# Stepoko.net
KiCad netlist of a schematic drawn in EAGLE
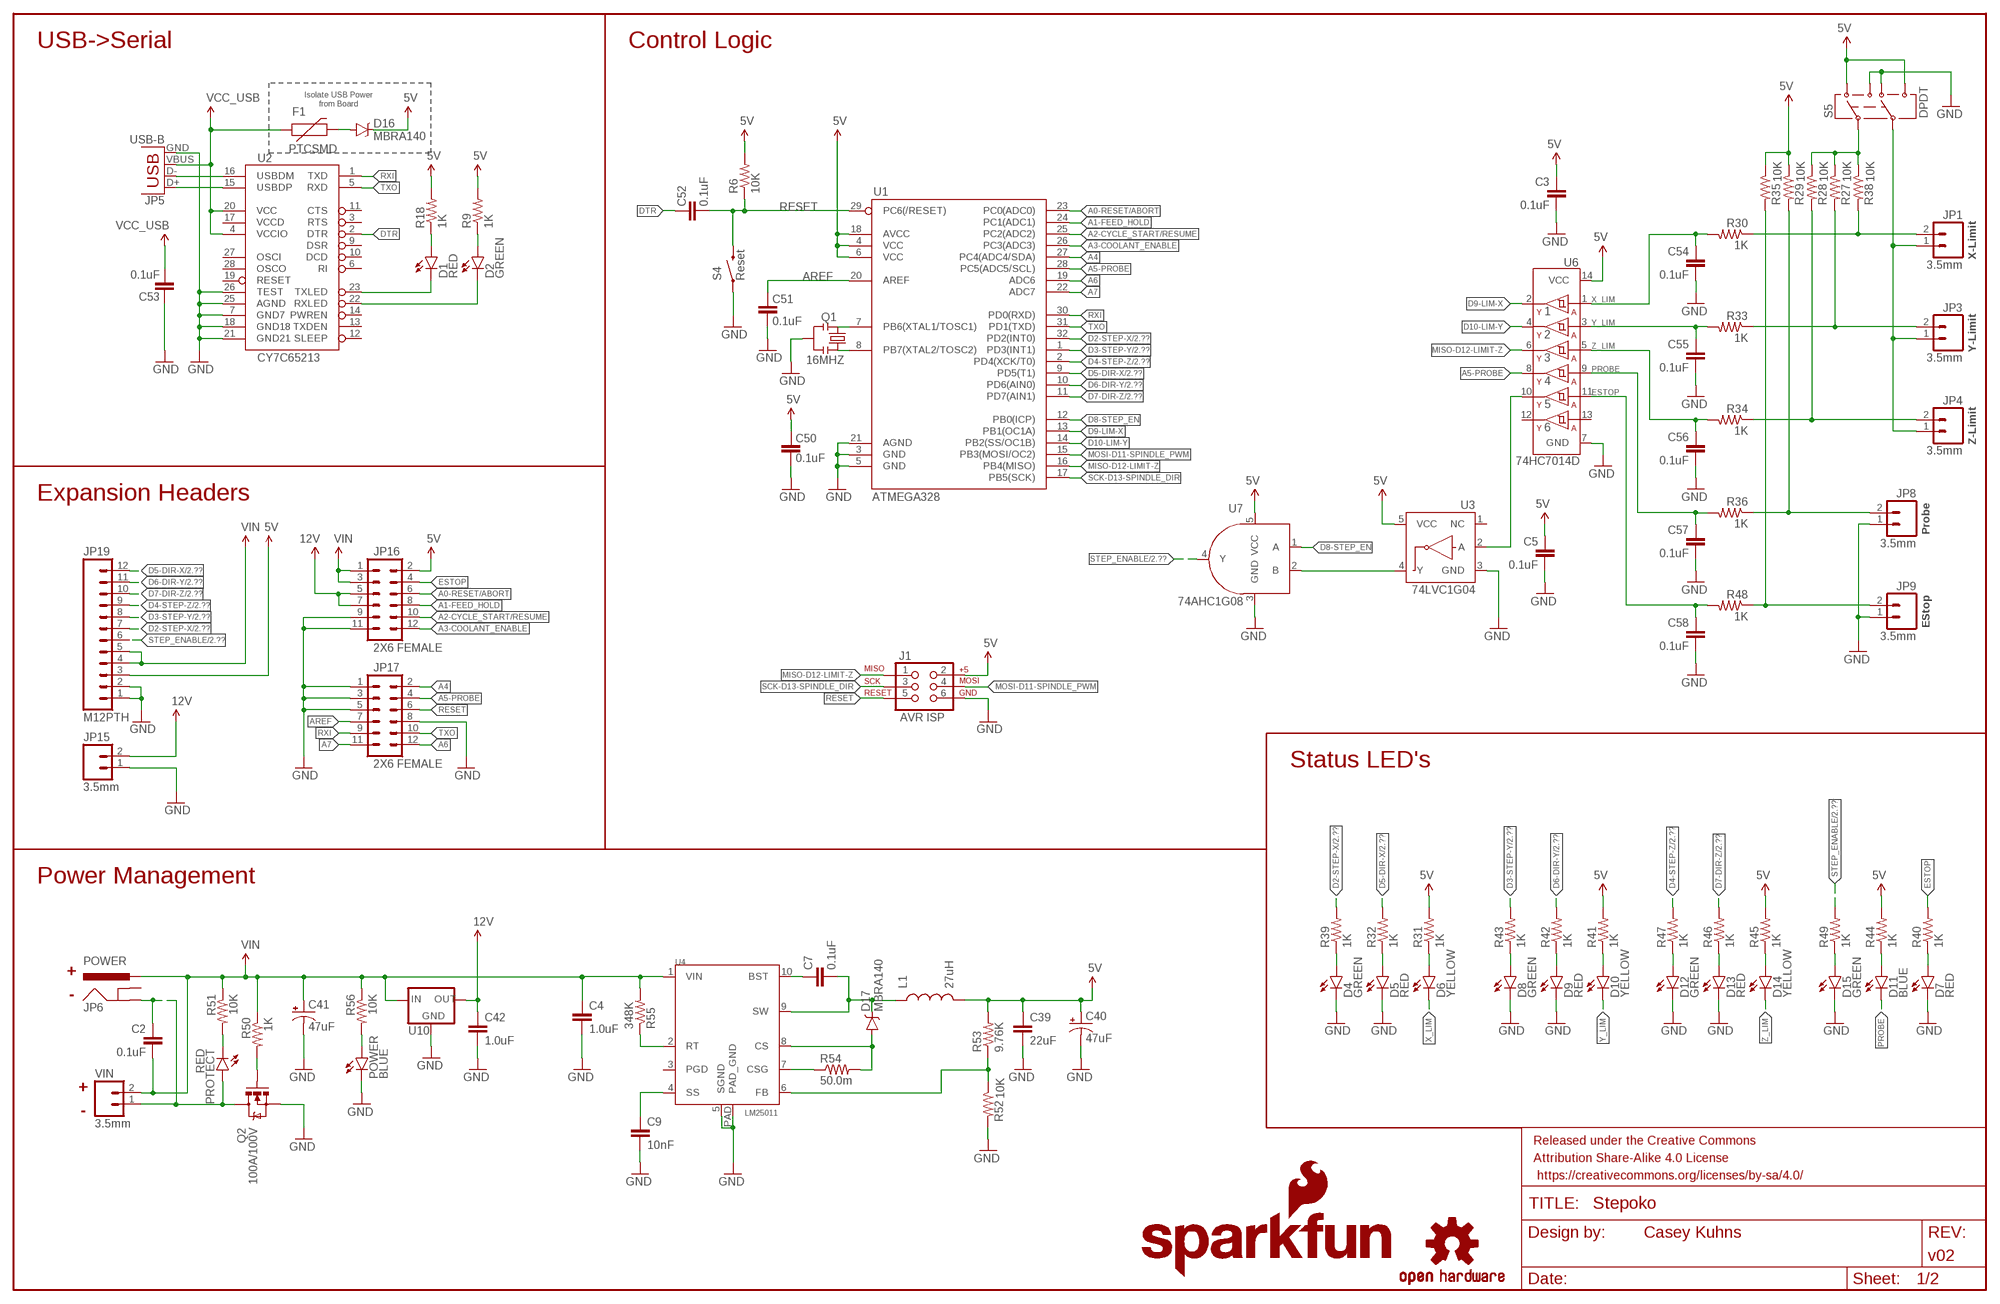
[diagram p0: schematic, sheet 1]
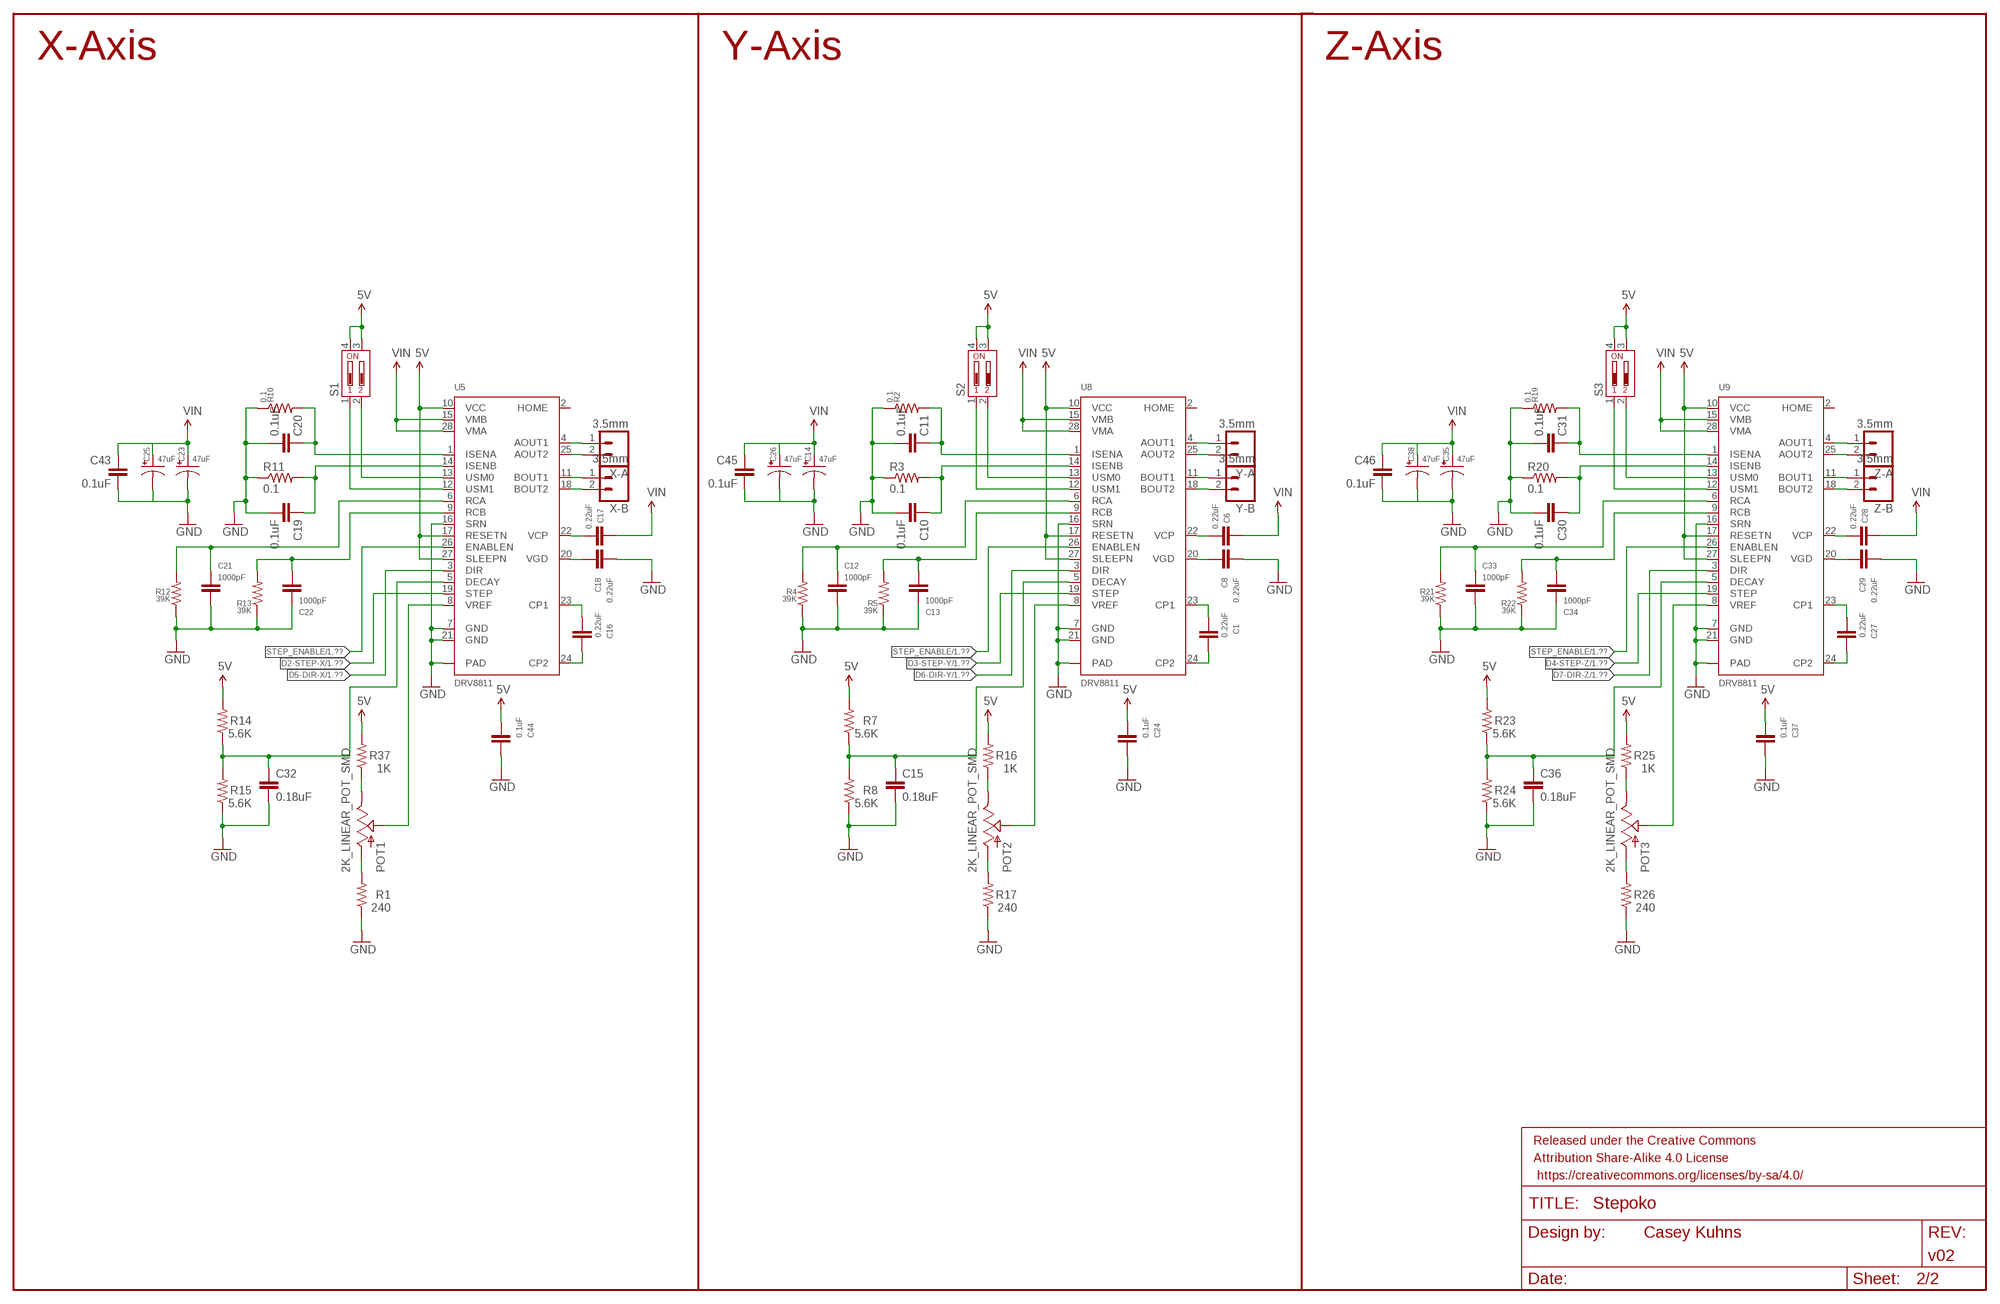
[diagram p1: schematic, sheet 2]

(export (version "E")
  (design (tool "Eeschema 10.0.6"))
  (components
    (comp (ref "C1")
      (value "0.22uF")
      (footprint "eagle-import:0603-CAP")
      (libsource (lib "eagle-import") (part "0.22UF50V-20%,+80%(0603)"))
    )
    (comp (ref "C6")
      (value "0.22uF")
      (footprint "eagle-import:0603-CAP")
      (libsource (lib "eagle-import") (part "0.22UF50V-20%,+80%(0603)"))
    )
    (comp (ref "C8")
      (value "0.22uF")
      (footprint "eagle-import:0603-CAP")
      (libsource (lib "eagle-import") (part "0.22UF50V-20%,+80%(0603)"))
    )
    (comp (ref "C10")
      (value "0.1uF")
      (footprint "eagle-import:0603-CAP")
      (libsource (lib "eagle-import") (part "0.1UF-25V(+80/-20%)(0603)"))
    )
    (comp (ref "C11")
      (value "0.1uF")
      (footprint "eagle-import:0603-CAP")
      (libsource (lib "eagle-import") (part "0.1UF-25V(+80/-20%)(0603)"))
    )
    (comp (ref "C12")
      (value "1000pF")
      (footprint "eagle-import:0603-CAP")
      (libsource (lib "eagle-import") (part "1NF/1000PF-50V-10%(0603)"))
    )
    (comp (ref "C13")
      (value "1000pF")
      (footprint "eagle-import:0603-CAP")
      (libsource (lib "eagle-import") (part "1NF/1000PF-50V-10%(0603)"))
    )
    (comp (ref "C14")
      (value "47uF")
      (footprint "eagle-import:PANASONIC_D")
      (libsource (lib "eagle-import") (part "47UF-50V-20%(ELECT)"))
    )
    (comp (ref "C15")
      (value "0.18uF")
      (footprint "eagle-import:0603")
      (libsource (lib "eagle-import") (part "0.18UF-10V(+-10%)(0603)"))
    )
    (comp (ref "C16")
      (value "0.22uF")
      (footprint "eagle-import:0603-CAP")
      (libsource (lib "eagle-import") (part "0.22UF50V-20%,+80%(0603)"))
    )
    (comp (ref "C17")
      (value "0.22uF")
      (footprint "eagle-import:0603-CAP")
      (libsource (lib "eagle-import") (part "0.22UF50V-20%,+80%(0603)"))
    )
    (comp (ref "C18")
      (value "0.22uF")
      (footprint "eagle-import:0603-CAP")
      (libsource (lib "eagle-import") (part "0.22UF50V-20%,+80%(0603)"))
    )
    (comp (ref "C19")
      (value "0.1uF")
      (footprint "eagle-import:0603-CAP")
      (libsource (lib "eagle-import") (part "0.1UF-25V(+80/-20%)(0603)"))
    )
    (comp (ref "C20")
      (value "0.1uF")
      (footprint "eagle-import:0603-CAP")
      (libsource (lib "eagle-import") (part "0.1UF-25V(+80/-20%)(0603)"))
    )
    (comp (ref "C21")
      (value "1000pF")
      (footprint "eagle-import:0603-CAP")
      (libsource (lib "eagle-import") (part "1NF/1000PF-50V-10%(0603)"))
    )
    (comp (ref "C22")
      (value "1000pF")
      (footprint "eagle-import:0603-CAP")
      (libsource (lib "eagle-import") (part "1NF/1000PF-50V-10%(0603)"))
    )
    (comp (ref "C23")
      (value "47uF")
      (footprint "eagle-import:PANASONIC_D")
      (libsource (lib "eagle-import") (part "47UF-50V-20%(ELECT)"))
    )
    (comp (ref "C24")
      (value "0.1uF")
      (footprint "eagle-import:0603-CAP")
      (libsource (lib "eagle-import") (part "0.1UF-25V(+80/-20%)(0603)"))
    )
    (comp (ref "C25")
      (value "47uF")
      (footprint "eagle-import:PANASONIC_D")
      (libsource (lib "eagle-import") (part "47UF-50V-20%(ELECT)"))
    )
    (comp (ref "C26")
      (value "47uF")
      (footprint "eagle-import:PANASONIC_D")
      (libsource (lib "eagle-import") (part "47UF-50V-20%(ELECT)"))
    )
    (comp (ref "C27")
      (value "0.22uF")
      (footprint "eagle-import:0603-CAP")
      (libsource (lib "eagle-import") (part "0.22UF50V-20%,+80%(0603)"))
    )
    (comp (ref "C28")
      (value "0.22uF")
      (footprint "eagle-import:0603-CAP")
      (libsource (lib "eagle-import") (part "0.22UF50V-20%,+80%(0603)"))
    )
    (comp (ref "C29")
      (value "0.22uF")
      (footprint "eagle-import:0603-CAP")
      (libsource (lib "eagle-import") (part "0.22UF50V-20%,+80%(0603)"))
    )
    (comp (ref "C30")
      (value "0.1uF")
      (footprint "eagle-import:0603-CAP")
      (libsource (lib "eagle-import") (part "0.1UF-25V(+80/-20%)(0603)"))
    )
    (comp (ref "C31")
      (value "0.1uF")
      (footprint "eagle-import:0603-CAP")
      (libsource (lib "eagle-import") (part "0.1UF-25V(+80/-20%)(0603)"))
    )
    (comp (ref "C32")
      (value "0.18uF")
      (footprint "eagle-import:0603")
      (libsource (lib "eagle-import") (part "0.18UF-10V(+-10%)(0603)"))
    )
    (comp (ref "C33")
      (value "1000pF")
      (footprint "eagle-import:0603-CAP")
      (libsource (lib "eagle-import") (part "1NF/1000PF-50V-10%(0603)"))
    )
    (comp (ref "C34")
      (value "1000pF")
      (footprint "eagle-import:0603-CAP")
      (libsource (lib "eagle-import") (part "1NF/1000PF-50V-10%(0603)"))
    )
    (comp (ref "C35")
      (value "47uF")
      (footprint "eagle-import:PANASONIC_D")
      (libsource (lib "eagle-import") (part "47UF-50V-20%(ELECT)"))
    )
    (comp (ref "C36")
      (value "0.18uF")
      (footprint "eagle-import:0603")
      (libsource (lib "eagle-import") (part "0.18UF-10V(+-10%)(0603)"))
    )
    (comp (ref "C37")
      (value "0.1uF")
      (footprint "eagle-import:0603-CAP")
      (libsource (lib "eagle-import") (part "0.1UF-25V(+80/-20%)(0603)"))
    )
    (comp (ref "C38")
      (value "47uF")
      (footprint "eagle-import:PANASONIC_D")
      (libsource (lib "eagle-import") (part "47UF-50V-20%(ELECT)"))
    )
    (comp (ref "C43")
      (value "0.1uF")
      (footprint "eagle-import:0603-CAP")
      (libsource (lib "eagle-import") (part "0.1UF-25V(+80/-20%)(0603)"))
    )
    (comp (ref "C44")
      (value "0.1uF")
      (footprint "eagle-import:0603-CAP")
      (libsource (lib "eagle-import") (part "0.1UF-25V(+80/-20%)(0603)"))
    )
    (comp (ref "C45")
      (value "0.1uF")
      (footprint "eagle-import:0603-CAP")
      (libsource (lib "eagle-import") (part "0.1UF-25V(+80/-20%)(0603)"))
    )
    (comp (ref "C46")
      (value "0.1uF")
      (footprint "eagle-import:0603-CAP")
      (libsource (lib "eagle-import") (part "0.1UF-25V(+80/-20%)(0603)"))
    )
    (comp (ref "FRAME2")
      (value "FRAME-LEDGER")
      (footprint "eagle-import:CREATIVE_COMMONS")
      (fields (field (name "DESIGNER") "Casey Kuhns") (field (name "VERSION") "v02"))
      (libsource (lib "eagle-import") (part "FRAME-LEDGER"))
    )
    (comp (ref "POT1")
      (value "2K_LINEAR_POT_SMD")
      (footprint "eagle-import:TC33X")
      (libsource (lib "eagle-import") (part "2K_LINEAR_POT_SMD"))
    )
    (comp (ref "POT2")
      (value "2K_LINEAR_POT_SMD")
      (footprint "eagle-import:TC33X")
      (libsource (lib "eagle-import") (part "2K_LINEAR_POT_SMD"))
    )
    (comp (ref "POT3")
      (value "2K_LINEAR_POT_SMD")
      (footprint "eagle-import:TC33X")
      (libsource (lib "eagle-import") (part "2K_LINEAR_POT_SMD"))
    )
    (comp (ref "R1")
      (value "240")
      (footprint "eagle-import:0603-RES")
      (libsource (lib "eagle-import") (part "240OHM1/10W1%(0603)"))
    )
    (comp (ref "R2")
      (value "0.1")
      (footprint "eagle-import:1210")
      (libsource (lib "eagle-import") (part "0.1OHM-1/2W-1%(1210)"))
    )
    (comp (ref "R3")
      (value "0.1")
      (footprint "eagle-import:1210")
      (libsource (lib "eagle-import") (part "0.1OHM-1/2W-1%(1210)"))
    )
    (comp (ref "R4")
      (value "39K")
      (footprint "eagle-import:0603")
      (libsource (lib "eagle-import") (part "39KOHM-1/10W-1%(0603)"))
    )
    (comp (ref "R5")
      (value "39K")
      (footprint "eagle-import:0603")
      (libsource (lib "eagle-import") (part "39KOHM-1/10W-1%(0603)"))
    )
    (comp (ref "R7")
      (value "5.6K")
      (footprint "eagle-import:0603")
      (libsource (lib "eagle-import") (part "5.6KOHM-1/10W-1%(0603)"))
    )
    (comp (ref "R8")
      (value "5.6K")
      (footprint "eagle-import:0603")
      (libsource (lib "eagle-import") (part "5.6KOHM-1/10W-1%(0603)"))
    )
    (comp (ref "R10")
      (value "0.1")
      (footprint "eagle-import:1210")
      (libsource (lib "eagle-import") (part "0.1OHM-1/2W-1%(1210)"))
    )
    (comp (ref "R11")
      (value "0.1")
      (footprint "eagle-import:1210")
      (libsource (lib "eagle-import") (part "0.1OHM-1/2W-1%(1210)"))
    )
    (comp (ref "R12")
      (value "39K")
      (footprint "eagle-import:0603")
      (libsource (lib "eagle-import") (part "39KOHM-1/10W-1%(0603)"))
    )
    (comp (ref "R13")
      (value "39K")
      (footprint "eagle-import:0603")
      (libsource (lib "eagle-import") (part "39KOHM-1/10W-1%(0603)"))
    )
    (comp (ref "R14")
      (value "5.6K")
      (footprint "eagle-import:0603")
      (libsource (lib "eagle-import") (part "5.6KOHM-1/10W-1%(0603)"))
    )
    (comp (ref "R15")
      (value "5.6K")
      (footprint "eagle-import:0603")
      (libsource (lib "eagle-import") (part "5.6KOHM-1/10W-1%(0603)"))
    )
    (comp (ref "R16")
      (value "1K")
      (footprint "eagle-import:0603-RES")
      (libsource (lib "eagle-import") (part "1KOHM-1/10W-1%(0603)"))
    )
    (comp (ref "R17")
      (value "240")
      (footprint "eagle-import:0603-RES")
      (libsource (lib "eagle-import") (part "240OHM1/10W1%(0603)"))
    )
    (comp (ref "R19")
      (value "0.1")
      (footprint "eagle-import:1210")
      (libsource (lib "eagle-import") (part "0.1OHM-1/2W-1%(1210)"))
    )
    (comp (ref "R20")
      (value "0.1")
      (footprint "eagle-import:1210")
      (libsource (lib "eagle-import") (part "0.1OHM-1/2W-1%(1210)"))
    )
    (comp (ref "R21")
      (value "39K")
      (footprint "eagle-import:0603")
      (libsource (lib "eagle-import") (part "39KOHM-1/10W-1%(0603)"))
    )
    (comp (ref "R22")
      (value "39K")
      (footprint "eagle-import:0603")
      (libsource (lib "eagle-import") (part "39KOHM-1/10W-1%(0603)"))
    )
    (comp (ref "R23")
      (value "5.6K")
      (footprint "eagle-import:0603")
      (libsource (lib "eagle-import") (part "5.6KOHM-1/10W-1%(0603)"))
    )
    (comp (ref "R24")
      (value "5.6K")
      (footprint "eagle-import:0603")
      (libsource (lib "eagle-import") (part "5.6KOHM-1/10W-1%(0603)"))
    )
    (comp (ref "R25")
      (value "1K")
      (footprint "eagle-import:0603-RES")
      (libsource (lib "eagle-import") (part "1KOHM-1/10W-1%(0603)"))
    )
    (comp (ref "R26")
      (value "240")
      (footprint "eagle-import:0603-RES")
      (libsource (lib "eagle-import") (part "240OHM1/10W1%(0603)"))
    )
    (comp (ref "R37")
      (value "1K")
      (footprint "eagle-import:0603-RES")
      (libsource (lib "eagle-import") (part "1KOHM-1/10W-1%(0603)"))
    )
    (comp (ref "S1")
      (value "2-POS-DIPCTS-THRU-HOLE")
      (footprint "eagle-import:209-2LPST")
      (libsource (lib "eagle-import") (part "2-POS-DIPCTS-THRU-HOLE"))
    )
    (comp (ref "S2")
      (value "2-POS-DIPCTS-THRU-HOLE")
      (footprint "eagle-import:209-2LPST")
      (libsource (lib "eagle-import") (part "2-POS-DIPCTS-THRU-HOLE"))
    )
    (comp (ref "S3")
      (value "2-POS-DIPCTS-THRU-HOLE")
      (footprint "eagle-import:209-2LPST")
      (libsource (lib "eagle-import") (part "2-POS-DIPCTS-THRU-HOLE"))
    )
    (comp (ref "U5")
      (value "DRV8811")
      (footprint "eagle-import:HTSSOP28")
      (libsource (lib "eagle-import") (part "DRV8811"))
    )
    (comp (ref "U8")
      (value "DRV8811")
      (footprint "eagle-import:HTSSOP28")
      (libsource (lib "eagle-import") (part "DRV8811"))
    )
    (comp (ref "U9")
      (value "DRV8811")
      (footprint "eagle-import:HTSSOP28")
      (libsource (lib "eagle-import") (part "DRV8811"))
    )
    (comp (ref "X-A")
      (value "3.5mm")
      (footprint "eagle-import:SCREWTERMINAL-3.5MM-2_LOCK")
      (libsource (lib "eagle-import") (part "M023.5MM_LOCK"))
    )
    (comp (ref "X-B")
      (value "3.5mm")
      (footprint "eagle-import:SCREWTERMINAL-3.5MM-2_LOCK")
      (libsource (lib "eagle-import") (part "M023.5MM_LOCK"))
    )
    (comp (ref "Y-A")
      (value "3.5mm")
      (footprint "eagle-import:SCREWTERMINAL-3.5MM-2_LOCK")
      (libsource (lib "eagle-import") (part "M023.5MM_LOCK"))
    )
    (comp (ref "Y-B")
      (value "3.5mm")
      (footprint "eagle-import:SCREWTERMINAL-3.5MM-2_LOCK")
      (libsource (lib "eagle-import") (part "M023.5MM_LOCK"))
    )
    (comp (ref "Z-A")
      (value "3.5mm")
      (footprint "eagle-import:SCREWTERMINAL-3.5MM-2_LOCK")
      (libsource (lib "eagle-import") (part "M023.5MM_LOCK"))
    )
    (comp (ref "Z-B")
      (value "3.5mm")
      (footprint "eagle-import:SCREWTERMINAL-3.5MM-2_LOCK")
      (libsource (lib "eagle-import") (part "M023.5MM_LOCK"))
    )
    (comp (ref "C2")
      (value "0.1uF")
      (footprint "eagle-import:0603-CAP")
      (libsource (lib "eagle-import") (part "0.1UF-100V-10%(0603)"))
    )
    (comp (ref "C3")
      (value "0.1uF")
      (footprint "eagle-import:0603-CAP")
      (libsource (lib "eagle-import") (part "0.1UF-25V(+80/-20%)(0603)"))
    )
    (comp (ref "C4")
      (value "1.0uF")
      (footprint "eagle-import:1206")
      (libsource (lib "eagle-import") (part "1.0UF50V10%(1206)"))
    )
    (comp (ref "C5")
      (value "0.1uF")
      (footprint "eagle-import:0603-CAP")
      (libsource (lib "eagle-import") (part "0.1UF-25V(+80/-20%)(0603)"))
    )
    (comp (ref "C7")
      (value "0.1uF")
      (footprint "eagle-import:0603-CAP")
      (libsource (lib "eagle-import") (part "0.1UF-25V(+80/-20%)(0603)"))
    )
    (comp (ref "C9")
      (value "10nF")
      (footprint "eagle-import:0603-CAP")
      (libsource (lib "eagle-import") (part "10NF/10000PF-50V-10%(0603)"))
    )
    (comp (ref "C39")
      (value "22uF")
      (footprint "eagle-import:1210")
      (libsource (lib "eagle-import") (part "22UF-16V-20%-(1210)"))
    )
    (comp (ref "C40")
      (value "47uF")
      (footprint "eagle-import:PANASONIC_D")
      (libsource (lib "eagle-import") (part "47UF-50V-20%(ELECT)"))
    )
    (comp (ref "C41")
      (value "47uF")
      (footprint "eagle-import:PANASONIC_D")
      (libsource (lib "eagle-import") (part "47UF-50V-20%(ELECT)"))
    )
    (comp (ref "C42")
      (value "1.0uF")
      (footprint "eagle-import:1206")
      (libsource (lib "eagle-import") (part "1.0UF50V10%(1206)"))
    )
    (comp (ref "C50")
      (value "0.1uF")
      (footprint "eagle-import:0603-CAP")
      (libsource (lib "eagle-import") (part "0.1UF-25V(+80/-20%)(0603)"))
    )
    (comp (ref "C51")
      (value "0.1uF")
      (footprint "eagle-import:0603-CAP")
      (libsource (lib "eagle-import") (part "0.1UF-25V(+80/-20%)(0603)"))
    )
    (comp (ref "C52")
      (value "0.1uF")
      (footprint "eagle-import:0603-CAP")
      (libsource (lib "eagle-import") (part "0.1UF-25V(+80/-20%)(0603)"))
    )
    (comp (ref "C53")
      (value "0.1uF")
      (footprint "eagle-import:0603-CAP")
      (libsource (lib "eagle-import") (part "0.1UF-25V(+80/-20%)(0603)"))
    )
    (comp (ref "C54")
      (value "0.1uF")
      (footprint "eagle-import:0603-CAP")
      (libsource (lib "eagle-import") (part "0.1UF-25V(+80/-20%)(0603)"))
    )
    (comp (ref "C55")
      (value "0.1uF")
      (footprint "eagle-import:0603-CAP")
      (libsource (lib "eagle-import") (part "0.1UF-25V(+80/-20%)(0603)"))
    )
    (comp (ref "C56")
      (value "0.1uF")
      (footprint "eagle-import:0603-CAP")
      (libsource (lib "eagle-import") (part "0.1UF-25V(+80/-20%)(0603)"))
    )
    (comp (ref "C57")
      (value "0.1uF")
      (footprint "eagle-import:0603-CAP")
      (libsource (lib "eagle-import") (part "0.1UF-25V(+80/-20%)(0603)"))
    )
    (comp (ref "C58")
      (value "0.1uF")
      (footprint "eagle-import:0603-CAP")
      (libsource (lib "eagle-import") (part "0.1UF-25V(+80/-20%)(0603)"))
    )
    (comp (ref "D1")
      (value "RED")
      (footprint "eagle-import:LED-1206")
      (libsource (lib "eagle-import") (part "LED-REDLILYPAD"))
    )
    (comp (ref "D2")
      (value "GREEN")
      (footprint "eagle-import:LED-1206")
      (libsource (lib "eagle-import") (part "LED-GREENLILYPAD"))
    )
    (comp (ref "D4")
      (value "GREEN")
      (footprint "eagle-import:LED-1206")
      (libsource (lib "eagle-import") (part "LED-GREENLILYPAD"))
    )
    (comp (ref "D5")
      (value "RED")
      (footprint "eagle-import:LED-1206")
      (libsource (lib "eagle-import") (part "LED-REDLILYPAD"))
    )
    (comp (ref "D6")
      (value "YELLOW")
      (footprint "eagle-import:LED-1206")
      (libsource (lib "eagle-import") (part "LED-YELLOWLILYPAD"))
    )
    (comp (ref "D7")
      (value "RED")
      (footprint "eagle-import:LED-1206")
      (libsource (lib "eagle-import") (part "LED-REDLILYPAD"))
    )
    (comp (ref "D8")
      (value "GREEN")
      (footprint "eagle-import:LED-1206")
      (libsource (lib "eagle-import") (part "LED-GREENLILYPAD"))
    )
    (comp (ref "D9")
      (value "RED")
      (footprint "eagle-import:LED-1206")
      (libsource (lib "eagle-import") (part "LED-REDLILYPAD"))
    )
    (comp (ref "D10")
      (value "YELLOW")
      (footprint "eagle-import:LED-1206")
      (libsource (lib "eagle-import") (part "LED-YELLOWLILYPAD"))
    )
    (comp (ref "D11")
      (value "BLUE")
      (footprint "eagle-import:LED-1206")
      (libsource (lib "eagle-import") (part "LED-BLUE1206"))
    )
    (comp (ref "D12")
      (value "GREEN")
      (footprint "eagle-import:LED-1206")
      (libsource (lib "eagle-import") (part "LED-GREENLILYPAD"))
    )
    (comp (ref "D13")
      (value "RED")
      (footprint "eagle-import:LED-1206")
      (libsource (lib "eagle-import") (part "LED-REDLILYPAD"))
    )
    (comp (ref "D14")
      (value "YELLOW")
      (footprint "eagle-import:LED-1206")
      (libsource (lib "eagle-import") (part "LED-YELLOWLILYPAD"))
    )
    (comp (ref "D15")
      (value "GREEN")
      (footprint "eagle-import:LED-1206")
      (libsource (lib "eagle-import") (part "LED-GREENLILYPAD"))
    )
    (comp (ref "D16")
      (value "MBRA140")
      (footprint "eagle-import:SMA-DIODE")
      (libsource (lib "eagle-import") (part "DIODE-SCHOTTKY-MBRA140"))
    )
    (comp (ref "D17")
      (value "MBRA140")
      (footprint "eagle-import:SMA-DIODE")
      (libsource (lib "eagle-import") (part "DIODE-SCHOTTKY-MBRA140"))
    )
    (comp (ref "F1")
      (value "PTCSMD")
      (footprint "eagle-import:PTC-1206")
      (libsource (lib "eagle-import") (part "PTCSMD"))
    )
    (comp (ref "FRAME1")
      (value "FRAME-LEDGER")
      (footprint "eagle-import:CREATIVE_COMMONS")
      (fields (field (name "DESIGNER") "Casey Kuhns") (field (name "VERSION") "v02"))
      (libsource (lib "eagle-import") (part "FRAME-LEDGER"))
    )
    (comp (ref "J1")
      (value "AVR ISP")
      (footprint "eagle-import:2X3")
      (libsource (lib "eagle-import") (part "AVR_SPI_PRG_6PTH"))
    )
    (comp (ref "JP1")
      (value "3.5mm")
      (footprint "eagle-import:SCREWTERMINAL-3.5MM-2_LOCK")
      (libsource (lib "eagle-import") (part "M023.5MM_LOCK"))
    )
    (comp (ref "JP3")
      (value "3.5mm")
      (footprint "eagle-import:SCREWTERMINAL-3.5MM-2_LOCK")
      (libsource (lib "eagle-import") (part "M023.5MM_LOCK"))
    )
    (comp (ref "JP4")
      (value "3.5mm")
      (footprint "eagle-import:SCREWTERMINAL-3.5MM-2_LOCK")
      (libsource (lib "eagle-import") (part "M023.5MM_LOCK"))
    )
    (comp (ref "JP5")
      (value "USB-B")
      (footprint "eagle-import:USB-B-PTH")
      (libsource (lib "eagle-import") (part "USBPTH"))
    )
    (comp (ref "JP6")
      (value "POWER")
      (footprint "eagle-import:POWER_JACK_PTH_LOCK")
      (libsource (lib "eagle-import") (part "POWER_JACKPTH_LOCK"))
    )
    (comp (ref "JP8")
      (value "3.5mm")
      (footprint "eagle-import:SCREWTERMINAL-3.5MM-2_LOCK")
      (libsource (lib "eagle-import") (part "M023.5MM_LOCK"))
    )
    (comp (ref "JP9")
      (value "3.5mm")
      (footprint "eagle-import:SCREWTERMINAL-3.5MM-2_LOCK")
      (libsource (lib "eagle-import") (part "M023.5MM_LOCK"))
    )
    (comp (ref "JP15")
      (value "3.5mm")
      (footprint "eagle-import:SCREWTERMINAL-3.5MM-2_LOCK")
      (libsource (lib "eagle-import") (part "M023.5MM_LOCK"))
    )
    (comp (ref "JP16")
      (value "2X6 FEMALE")
      (footprint "eagle-import:2X6")
      (libsource (lib "eagle-import") (part "M06X2PTH_FEMALE"))
    )
    (comp (ref "JP17")
      (value "2X6 FEMALE")
      (footprint "eagle-import:2X6")
      (libsource (lib "eagle-import") (part "M06X2PTH_FEMALE"))
    )
    (comp (ref "JP19")
      (value "M12PTH")
      (footprint "eagle-import:1X12")
      (libsource (lib "eagle-import") (part "M12PTH"))
    )
    (comp (ref "L1")
      (value "27uH")
      (footprint "eagle-import:INDUCTOR_SDR1307")
      (libsource (lib "eagle-import") (part "INDUCTORSDR13-7-270ML"))
    )
    (comp (ref "LOGO1")
      (value "OSHW-LOGOM")
      (footprint "eagle-import:OSHW-LOGO-M")
      (libsource (lib "eagle-import") (part "OSHW-LOGOM"))
    )
    (comp (ref "LOGO2")
      (value "SFE_LOGO_NAME_FLAME.2_INCH")
      (footprint "eagle-import:SFE_LOGO_NAME_FLAME_.2")
      (libsource (lib "eagle-import") (part "SFE_LOGO_NAME_FLAME.2_INCH"))
    )
    (comp (ref "POWER")
      (value "BLUE")
      (footprint "eagle-import:LED-1206")
      (libsource (lib "eagle-import") (part "LED-BLUE1206"))
    )
    (comp (ref "PROTECT")
      (value "RED")
      (footprint "eagle-import:LED-1206")
      (libsource (lib "eagle-import") (part "LED-REDLILYPAD"))
    )
    (comp (ref "Q1")
      (value "16MHZ")
      (footprint "eagle-import:RESONATOR-SMD")
      (libsource (lib "eagle-import") (part "RESONATOR16MHZ"))
    )
    (comp (ref "Q2")
      (value "100A/100V")
      (footprint "eagle-import:TO-263_D2PAK")
      (libsource (lib "eagle-import") (part "MOSFET-NCHANNELPSMN7R0"))
    )
    (comp (ref "R6")
      (value "10K")
      (footprint "eagle-import:0603-RES")
      (libsource (lib "eagle-import") (part "10KOHM-1/10W-1%(0603)0603"))
    )
    (comp (ref "R9")
      (value "1K")
      (footprint "eagle-import:0603-RES")
      (libsource (lib "eagle-import") (part "1KOHM1/10W1%(0603)"))
    )
    (comp (ref "R18")
      (value "1K")
      (footprint "eagle-import:0603-RES")
      (libsource (lib "eagle-import") (part "1KOHM1/10W1%(0603)"))
    )
    (comp (ref "R27")
      (value "10K")
      (footprint "eagle-import:0603-RES")
      (libsource (lib "eagle-import") (part "10KOHM-1/10W-1%(0603)0603"))
    )
    (comp (ref "R28")
      (value "10K")
      (footprint "eagle-import:0603-RES")
      (libsource (lib "eagle-import") (part "10KOHM-1/10W-1%(0603)0603"))
    )
    (comp (ref "R29")
      (value "10K")
      (footprint "eagle-import:0603-RES")
      (libsource (lib "eagle-import") (part "10KOHM-1/10W-1%(0603)0603"))
    )
    (comp (ref "R30")
      (value "1K")
      (footprint "eagle-import:0603-RES")
      (libsource (lib "eagle-import") (part "1KOHM1/10W1%(0603)"))
    )
    (comp (ref "R31")
      (value "1K")
      (footprint "eagle-import:0603-RES")
      (libsource (lib "eagle-import") (part "1KOHM-1/10W-1%(0603)"))
    )
    (comp (ref "R32")
      (value "1K")
      (footprint "eagle-import:0603-RES")
      (libsource (lib "eagle-import") (part "1KOHM-1/10W-1%(0603)"))
    )
    (comp (ref "R33")
      (value "1K")
      (footprint "eagle-import:0603-RES")
      (libsource (lib "eagle-import") (part "1KOHM1/10W1%(0603)"))
    )
    (comp (ref "R34")
      (value "1K")
      (footprint "eagle-import:0603-RES")
      (libsource (lib "eagle-import") (part "1KOHM1/10W1%(0603)"))
    )
    (comp (ref "R35")
      (value "10K")
      (footprint "eagle-import:0603-RES")
      (libsource (lib "eagle-import") (part "10KOHM-1/10W-1%(0603)0603"))
    )
    (comp (ref "R36")
      (value "1K")
      (footprint "eagle-import:0603-RES")
      (libsource (lib "eagle-import") (part "1KOHM1/10W1%(0603)"))
    )
    (comp (ref "R38")
      (value "10K")
      (footprint "eagle-import:0603-RES")
      (libsource (lib "eagle-import") (part "10KOHM-1/10W-1%(0603)0603"))
    )
    (comp (ref "R39")
      (value "1K")
      (footprint "eagle-import:0603-RES")
      (libsource (lib "eagle-import") (part "1KOHM-1/10W-1%(0603)"))
    )
    (comp (ref "R40")
      (value "1K")
      (footprint "eagle-import:0603-RES")
      (libsource (lib "eagle-import") (part "1KOHM-1/10W-1%(0603)"))
    )
    (comp (ref "R41")
      (value "1K")
      (footprint "eagle-import:0603-RES")
      (libsource (lib "eagle-import") (part "1KOHM-1/10W-1%(0603)"))
    )
    (comp (ref "R42")
      (value "1K")
      (footprint "eagle-import:0603-RES")
      (libsource (lib "eagle-import") (part "1KOHM-1/10W-1%(0603)"))
    )
    (comp (ref "R43")
      (value "1K")
      (footprint "eagle-import:0603-RES")
      (libsource (lib "eagle-import") (part "1KOHM-1/10W-1%(0603)"))
    )
    (comp (ref "R44")
      (value "1K")
      (footprint "eagle-import:0603-RES")
      (libsource (lib "eagle-import") (part "1KOHM-1/10W-1%(0603)"))
    )
    (comp (ref "R45")
      (value "1K")
      (footprint "eagle-import:0603-RES")
      (libsource (lib "eagle-import") (part "1KOHM-1/10W-1%(0603)"))
    )
    (comp (ref "R46")
      (value "1K")
      (footprint "eagle-import:0603-RES")
      (libsource (lib "eagle-import") (part "1KOHM-1/10W-1%(0603)"))
    )
    (comp (ref "R47")
      (value "1K")
      (footprint "eagle-import:0603-RES")
      (libsource (lib "eagle-import") (part "1KOHM-1/10W-1%(0603)"))
    )
    (comp (ref "R48")
      (value "1K")
      (footprint "eagle-import:0603-RES")
      (libsource (lib "eagle-import") (part "1KOHM1/10W1%(0603)"))
    )
    (comp (ref "R49")
      (value "1K")
      (footprint "eagle-import:0603-RES")
      (libsource (lib "eagle-import") (part "1KOHM-1/10W-1%(0603)"))
    )
    (comp (ref "R50")
      (value "1K")
      (footprint "eagle-import:0603-RES")
      (libsource (lib "eagle-import") (part "1KOHM1/10W1%(0603)"))
    )
    (comp (ref "R51")
      (value "10K")
      (footprint "eagle-import:0603-RES")
      (libsource (lib "eagle-import") (part "10KOHM-1/10W-1%(0603)0603"))
    )
    (comp (ref "R52")
      (value "10K")
      (footprint "eagle-import:0603-RES")
      (libsource (lib "eagle-import") (part "10KOHM-1/10W-1%(0603)0603"))
    )
    (comp (ref "R53")
      (value "9.76K")
      (footprint "eagle-import:0603")
      (libsource (lib "eagle-import") (part "9.76KOHM-1/10W-1%(0603)"))
    )
    (comp (ref "R54")
      (value "50.0m")
      (footprint "eagle-import:0603")
      (libsource (lib "eagle-import") (part "0.05OHM-1/5W-1%(0603)"))
    )
    (comp (ref "R55")
      (value "348K")
      (footprint "eagle-import:0603")
      (libsource (lib "eagle-import") (part "348KOHM-1/10W-1%(0603)"))
    )
    (comp (ref "R56")
      (value "10K")
      (footprint "eagle-import:0603-RES")
      (libsource (lib "eagle-import") (part "10KOHM-1/10W-1%(0603)0603"))
    )
    (comp (ref "S4")
      (value "Reset")
      (footprint "eagle-import:TACTILE-SWITCH-SMD")
      (libsource (lib "eagle-import") (part "SWITCH-MOMENTARY-2SMD"))
    )
    (comp (ref "S5")
      (value "DPDT")
      (footprint "eagle-import:AYZ0202")
      (libsource (lib "eagle-import") (part "SWITCH-DPDTAYZ0202"))
    )
    (comp (ref "U1")
      (value "ATMEGA328")
      (footprint "eagle-import:TQFP32-08")
      (libsource (lib "eagle-import") (part "ATMEGA328_SMT"))
    )
    (comp (ref "U2")
      (value "CY7C65213")
      (footprint "eagle-import:SSOP28DB")
      (libsource (lib "eagle-import") (part "CY7C65213"))
    )
    (comp (ref "U3")
      (value "74LVC1G04")
      (footprint "eagle-import:SOT353")
      (libsource (lib "eagle-import") (part "INVERTER_SOT353-5"))
    )
    (comp (ref "U4")
      (value "LM25011")
      (footprint "eagle-import:HVSS0P-10")
      (libsource (lib "eagle-import") (part "LM25011"))
    )
    (comp (ref "U6")
      (value "74HC7014D")
      (footprint "eagle-import:SOIC-14")
      (libsource (lib "eagle-import") (part "74HC7014D"))
    )
    (comp (ref "U7")
      (value "74AHC1G08")
      (footprint "eagle-import:SOT23-5")
      (libsource (lib "eagle-import") (part "74AHC1G08"))
    )
    (comp (ref "U10")
      (value "V_REG_78XX7812")
      (footprint "eagle-import:TO-252")
      (libsource (lib "eagle-import") (part "V_REG_78XX7812"))
    )
    (comp (ref "VIN")
      (value "3.5mm")
      (footprint "eagle-import:SCREWTERMINAL-3.5MM-2_LOCK")
      (libsource (lib "eagle-import") (part "M023.5MM_LOCK"))
    )
  )
  (nets
    (net (code "1") (name "5V") (class "Default")
      (node (ref "C24") (pin "1") (pinfunction "1_1") (pintype "passive"))
      (node (ref "C3") (pin "1") (pinfunction "1_1") (pintype "passive"))
      (node (ref "C37") (pin "1") (pinfunction "1_1") (pintype "passive"))
      (node (ref "C39") (pin "1") (pinfunction "1_1") (pintype "passive"))
      (node (ref "C40") (pin "+") (pinfunction "+_+") (pintype "passive"))
      (node (ref "C44") (pin "1") (pinfunction "1_1") (pintype "passive"))
      (node (ref "C5") (pin "1") (pinfunction "1_1") (pintype "passive"))
      (node (ref "C50") (pin "2") (pinfunction "2_2") (pintype "passive"))
      (node (ref "D16") (pin "C") (pinfunction "C_C") (pintype "passive"))
      (node (ref "J1") (pin "2") (pinfunction "2_2") (pintype "passive"))
      (node (ref "JP16") (pin "2") (pinfunction "2_2") (pintype "passive"))
      (node (ref "JP19") (pin "3") (pinfunction "3_3") (pintype "passive"))
      (node (ref "L1") (pin "P$2") (pinfunction "2_P$2") (pintype "passive"))
      (node (ref "R14") (pin "2") (pinfunction "2_2") (pintype "passive"))
      (node (ref "R16") (pin "2") (pinfunction "2_2") (pintype "passive"))
      (node (ref "R18") (pin "2") (pinfunction "2_2") (pintype "passive"))
      (node (ref "R23") (pin "2") (pinfunction "2_2") (pintype "passive"))
      (node (ref "R25") (pin "2") (pinfunction "2_2") (pintype "passive"))
      (node (ref "R29") (pin "1") (pinfunction "1_1") (pintype "passive"))
      (node (ref "R31") (pin "2") (pinfunction "2_2") (pintype "passive"))
      (node (ref "R35") (pin "1") (pinfunction "1_1") (pintype "passive"))
      (node (ref "R37") (pin "2") (pinfunction "2_2") (pintype "passive"))
      (node (ref "R41") (pin "2") (pinfunction "2_2") (pintype "passive"))
      (node (ref "R44") (pin "2") (pinfunction "2_2") (pintype "passive"))
      (node (ref "R45") (pin "2") (pinfunction "2_2") (pintype "passive"))
      (node (ref "R53") (pin "2") (pinfunction "2_2") (pintype "passive"))
      (node (ref "R6") (pin "2") (pinfunction "2_2") (pintype "passive"))
      (node (ref "R7") (pin "2") (pinfunction "2_2") (pintype "passive"))
      (node (ref "R9") (pin "2") (pinfunction "2_2") (pintype "passive"))
      (node (ref "S1") (pin "3") (pinfunction "P$3_3") (pintype "bidirectional"))
      (node (ref "S1") (pin "4") (pinfunction "P$4_4") (pintype "bidirectional"))
      (node (ref "S2") (pin "3") (pinfunction "P$3_3") (pintype "bidirectional"))
      (node (ref "S2") (pin "4") (pinfunction "P$4_4") (pintype "bidirectional"))
      (node (ref "S3") (pin "3") (pinfunction "P$3_3") (pintype "bidirectional"))
      (node (ref "S3") (pin "4") (pinfunction "P$4_4") (pintype "bidirectional"))
      (node (ref "S5") (pin "1") (pinfunction "1_1") (pintype "bidirectional"))
      (node (ref "S5") (pin "6") (pinfunction "6_6") (pintype "bidirectional"))
      (node (ref "U1") (pin "18") (pinfunction "AVCC_18") (pintype "bidirectional"))
      (node (ref "U1") (pin "4") (pinfunction "VCC_4") (pintype "bidirectional"))
      (node (ref "U1") (pin "6") (pinfunction "VCC_6") (pintype "bidirectional"))
      (node (ref "U3") (pin "5") (pinfunction "VCC_5") (pintype "bidirectional"))
      (node (ref "U5") (pin "10") (pinfunction "VCC_10") (pintype "bidirectional"))
      (node (ref "U5") (pin "17") (pinfunction "RESETN_17") (pintype "bidirectional"))
      (node (ref "U5") (pin "27") (pinfunction "SLEEPN_27") (pintype "bidirectional"))
      (node (ref "U6") (pin "14") (pinfunction "VCC_14") (pintype "power_in"))
      (node (ref "U7") (pin "5") (pinfunction "VCC_5") (pintype "bidirectional"))
      (node (ref "U8") (pin "10") (pinfunction "VCC_10") (pintype "bidirectional"))
      (node (ref "U8") (pin "17") (pinfunction "RESETN_17") (pintype "bidirectional"))
      (node (ref "U8") (pin "27") (pinfunction "SLEEPN_27") (pintype "bidirectional"))
      (node (ref "U9") (pin "10") (pinfunction "VCC_10") (pintype "bidirectional"))
      (node (ref "U9") (pin "17") (pinfunction "RESETN_17") (pintype "bidirectional"))
      (node (ref "U9") (pin "27") (pinfunction "SLEEPN_27") (pintype "bidirectional"))
    )
    (net (code "2") (name "A0-RESET{slash}ABORT") (class "Default")
      (node (ref "JP16") (pin "6") (pinfunction "6_6") (pintype "passive"))
      (node (ref "U1") (pin "23") (pinfunction "PC0(ADC0)_23") (pintype "bidirectional"))
    )
    (net (code "3") (name "A1-FEED_HOLD") (class "Default")
      (node (ref "JP16") (pin "8") (pinfunction "8_8") (pintype "passive"))
      (node (ref "U1") (pin "24") (pinfunction "PC1(ADC1)_24") (pintype "bidirectional"))
    )
    (net (code "4") (name "A2-CYCLE_START{slash}RESUME") (class "Default")
      (node (ref "JP16") (pin "10") (pinfunction "10_10") (pintype "passive"))
      (node (ref "U1") (pin "25") (pinfunction "PC2(ADC2)_25") (pintype "bidirectional"))
    )
    (net (code "5") (name "A3-COOLANT_ENABLE") (class "Default")
      (node (ref "JP16") (pin "12") (pinfunction "12_12") (pintype "passive"))
      (node (ref "U1") (pin "26") (pinfunction "PC3(ADC3)_26") (pintype "bidirectional"))
    )
    (net (code "6") (name "A4") (class "Default")
      (node (ref "JP17") (pin "2") (pinfunction "2_2") (pintype "passive"))
      (node (ref "U1") (pin "27") (pinfunction "PC4(ADC4/SDA)_27") (pintype "bidirectional"))
    )
    (net (code "7") (name "A5-PROBE") (class "Default")
      (node (ref "JP17") (pin "4") (pinfunction "4_4") (pintype "passive"))
      (node (ref "U1") (pin "28") (pinfunction "PC5(ADC5/SCL)_28") (pintype "bidirectional"))
      (node (ref "U6") (pin "8") (pinfunction "4Y_8") (pintype "output"))
    )
    (net (code "8") (name "A6") (class "Default")
      (node (ref "JP17") (pin "12") (pinfunction "12_12") (pintype "passive"))
      (node (ref "U1") (pin "19") (pinfunction "ADC6_19") (pintype "bidirectional"))
    )
    (net (code "9") (name "A7") (class "Default")
      (node (ref "JP17") (pin "11") (pinfunction "11_11") (pintype "passive"))
      (node (ref "U1") (pin "22") (pinfunction "ADC7_22") (pintype "bidirectional"))
    )
    (net (code "10") (name "AREF") (class "Default")
      (node (ref "C51") (pin "2") (pinfunction "2_2") (pintype "passive"))
      (node (ref "JP17") (pin "7") (pinfunction "7_7") (pintype "passive"))
      (node (ref "U1") (pin "20") (pinfunction "AREF_20") (pintype "bidirectional"))
    )
    (net (code "11") (name "D2-STEP-X") (class "Default")
      (node (ref "JP19") (pin "7") (pinfunction "7_7") (pintype "passive"))
      (node (ref "R39") (pin "2") (pinfunction "2_2") (pintype "passive"))
      (node (ref "U1") (pin "32") (pinfunction "PD2(INT0)_32") (pintype "bidirectional"))
      (node (ref "U5") (pin "19") (pinfunction "STEP_19") (pintype "bidirectional"))
    )
    (net (code "12") (name "D3-STEP-Y") (class "Default")
      (node (ref "JP19") (pin "8") (pinfunction "8_8") (pintype "passive"))
      (node (ref "R43") (pin "2") (pinfunction "2_2") (pintype "passive"))
      (node (ref "U1") (pin "1") (pinfunction "PD3(INT1)_1") (pintype "bidirectional"))
      (node (ref "U8") (pin "19") (pinfunction "STEP_19") (pintype "bidirectional"))
    )
    (net (code "13") (name "D4-STEP-Z") (class "Default")
      (node (ref "JP19") (pin "9") (pinfunction "9_9") (pintype "passive"))
      (node (ref "R47") (pin "2") (pinfunction "2_2") (pintype "passive"))
      (node (ref "U1") (pin "2") (pinfunction "PD4(XCK/T0)_2") (pintype "bidirectional"))
      (node (ref "U9") (pin "19") (pinfunction "STEP_19") (pintype "bidirectional"))
    )
    (net (code "14") (name "D5-DIR-X") (class "Default")
      (node (ref "JP19") (pin "12") (pinfunction "12_12") (pintype "passive"))
      (node (ref "R32") (pin "2") (pinfunction "2_2") (pintype "passive"))
      (node (ref "U1") (pin "9") (pinfunction "PD5(T1)_9") (pintype "bidirectional"))
      (node (ref "U5") (pin "3") (pinfunction "DIR_3") (pintype "bidirectional"))
    )
    (net (code "15") (name "D6-DIR-Y") (class "Default")
      (node (ref "JP19") (pin "11") (pinfunction "11_11") (pintype "passive"))
      (node (ref "R42") (pin "2") (pinfunction "2_2") (pintype "passive"))
      (node (ref "U1") (pin "10") (pinfunction "PD6(AIN0)_10") (pintype "bidirectional"))
      (node (ref "U8") (pin "3") (pinfunction "DIR_3") (pintype "bidirectional"))
    )
    (net (code "16") (name "D7-DIR-Z") (class "Default")
      (node (ref "JP19") (pin "10") (pinfunction "10_10") (pintype "passive"))
      (node (ref "R46") (pin "2") (pinfunction "2_2") (pintype "passive"))
      (node (ref "U1") (pin "11") (pinfunction "PD7(AIN1)_11") (pintype "bidirectional"))
      (node (ref "U9") (pin "3") (pinfunction "DIR_3") (pintype "bidirectional"))
    )
    (net (code "17") (name "D8-STEP_EN") (class "Default")
      (node (ref "U1") (pin "12") (pinfunction "PB0(ICP)_12") (pintype "bidirectional"))
      (node (ref "U7") (pin "1") (pinfunction "A_1") (pintype "bidirectional"))
    )
    (net (code "18") (name "D9-LIM-X") (class "Default")
      (node (ref "U1") (pin "13") (pinfunction "PB1(OC1A)_13") (pintype "bidirectional"))
      (node (ref "U6") (pin "2") (pinfunction "1Y_2") (pintype "output"))
    )
    (net (code "19") (name "D10-LIM-Y") (class "Default")
      (node (ref "U1") (pin "14") (pinfunction "PB2(SS/OC1B)_14") (pintype "bidirectional"))
      (node (ref "U6") (pin "4") (pinfunction "2Y_4") (pintype "output"))
    )
    (net (code "20") (name "DTR") (class "Default")
      (node (ref "C52") (pin "2") (pinfunction "2_2") (pintype "passive"))
      (node (ref "U2") (pin "2") (pinfunction "DTR_2") (pintype "output"))
    )
    (net (code "21") (name "ESTOP") (class "Default")
      (node (ref "C58") (pin "1") (pinfunction "1_1") (pintype "passive"))
      (node (ref "JP16") (pin "4") (pinfunction "4_4") (pintype "passive"))
      (node (ref "R40") (pin "2") (pinfunction "2_2") (pintype "passive"))
      (node (ref "R48") (pin "2") (pinfunction "2_2") (pintype "passive"))
      (node (ref "U6") (pin "11") (pinfunction "5A_11") (pintype "input"))
    )
    (net (code "22") (name "GND") (class "Default")
      (node (ref "C10") (pin "2") (pinfunction "2_2") (pintype "passive"))
      (node (ref "C11") (pin "2") (pinfunction "2_2") (pintype "passive"))
      (node (ref "C12") (pin "2") (pinfunction "2_2") (pintype "passive"))
      (node (ref "C13") (pin "2") (pinfunction "2_2") (pintype "passive"))
      (node (ref "C14") (pin "-") (pinfunction "-_-") (pintype "passive"))
      (node (ref "C15") (pin "2") (pinfunction "2_2") (pintype "passive"))
      (node (ref "C18") (pin "1") (pinfunction "1_1") (pintype "passive"))
      (node (ref "C19") (pin "2") (pinfunction "2_2") (pintype "passive"))
      (node (ref "C20") (pin "2") (pinfunction "2_2") (pintype "passive"))
      (node (ref "C21") (pin "2") (pinfunction "2_2") (pintype "passive"))
      (node (ref "C22") (pin "2") (pinfunction "2_2") (pintype "passive"))
      (node (ref "C23") (pin "-") (pinfunction "-_-") (pintype "passive"))
      (node (ref "C24") (pin "2") (pinfunction "2_2") (pintype "passive"))
      (node (ref "C25") (pin "-") (pinfunction "-_-") (pintype "passive"))
      (node (ref "C26") (pin "-") (pinfunction "-_-") (pintype "passive"))
      (node (ref "C29") (pin "1") (pinfunction "1_1") (pintype "passive"))
      (node (ref "C3") (pin "2") (pinfunction "2_2") (pintype "passive"))
      (node (ref "C30") (pin "2") (pinfunction "2_2") (pintype "passive"))
      (node (ref "C31") (pin "2") (pinfunction "2_2") (pintype "passive"))
      (node (ref "C32") (pin "2") (pinfunction "2_2") (pintype "passive"))
      (node (ref "C33") (pin "2") (pinfunction "2_2") (pintype "passive"))
      (node (ref "C34") (pin "2") (pinfunction "2_2") (pintype "passive"))
      (node (ref "C35") (pin "-") (pinfunction "-_-") (pintype "passive"))
      (node (ref "C36") (pin "2") (pinfunction "2_2") (pintype "passive"))
      (node (ref "C37") (pin "2") (pinfunction "2_2") (pintype "passive"))
      (node (ref "C38") (pin "-") (pinfunction "-_-") (pintype "passive"))
      (node (ref "C39") (pin "2") (pinfunction "2_2") (pintype "passive"))
      (node (ref "C4") (pin "2") (pinfunction "2_2") (pintype "passive"))
      (node (ref "C40") (pin "-") (pinfunction "-_-") (pintype "passive"))
      (node (ref "C41") (pin "-") (pinfunction "-_-") (pintype "passive"))
      (node (ref "C42") (pin "2") (pinfunction "2_2") (pintype "passive"))
      (node (ref "C43") (pin "2") (pinfunction "2_2") (pintype "passive"))
      (node (ref "C44") (pin "2") (pinfunction "2_2") (pintype "passive"))
      (node (ref "C45") (pin "2") (pinfunction "2_2") (pintype "passive"))
      (node (ref "C46") (pin "2") (pinfunction "2_2") (pintype "passive"))
      (node (ref "C5") (pin "2") (pinfunction "2_2") (pintype "passive"))
      (node (ref "C50") (pin "1") (pinfunction "1_1") (pintype "passive"))
      (node (ref "C51") (pin "1") (pinfunction "1_1") (pintype "passive"))
      (node (ref "C53") (pin "2") (pinfunction "2_2") (pintype "passive"))
      (node (ref "C54") (pin "2") (pinfunction "2_2") (pintype "passive"))
      (node (ref "C55") (pin "2") (pinfunction "2_2") (pintype "passive"))
      (node (ref "C56") (pin "2") (pinfunction "2_2") (pintype "passive"))
      (node (ref "C57") (pin "2") (pinfunction "2_2") (pintype "passive"))
      (node (ref "C58") (pin "2") (pinfunction "2_2") (pintype "passive"))
      (node (ref "C8") (pin "1") (pinfunction "1_1") (pintype "passive"))
      (node (ref "C9") (pin "2") (pinfunction "2_2") (pintype "passive"))
      (node (ref "D12") (pin "C") (pinfunction "C_C") (pintype "passive"))
      (node (ref "D13") (pin "C") (pinfunction "C_C") (pintype "passive"))
      (node (ref "D15") (pin "C") (pinfunction "C_C") (pintype "passive"))
      (node (ref "D4") (pin "C") (pinfunction "C_C") (pintype "passive"))
      (node (ref "D5") (pin "C") (pinfunction "C_C") (pintype "passive"))
      (node (ref "D7") (pin "C") (pinfunction "C_C") (pintype "passive"))
      (node (ref "D8") (pin "C") (pinfunction "C_C") (pintype "passive"))
      (node (ref "D9") (pin "C") (pinfunction "C_C") (pintype "passive"))
      (node (ref "J1") (pin "6") (pinfunction "6_6") (pintype "passive"))
      (node (ref "JP15") (pin "1") (pinfunction "1_1") (pintype "passive"))
      (node (ref "JP16") (pin "11") (pinfunction "11_11") (pintype "passive"))
      (node (ref "JP16") (pin "9") (pinfunction "9_9") (pintype "passive"))
      (node (ref "JP17") (pin "1") (pinfunction "1_1") (pintype "passive"))
      (node (ref "JP17") (pin "3") (pinfunction "3_3") (pintype "passive"))
      (node (ref "JP17") (pin "5") (pinfunction "5_5") (pintype "passive"))
      (node (ref "JP17") (pin "8") (pinfunction "8_8") (pintype "passive"))
      (node (ref "JP19") (pin "1") (pinfunction "1_1") (pintype "passive"))
      (node (ref "JP19") (pin "2") (pinfunction "2_2") (pintype "passive"))
      (node (ref "JP5") (pin "GND") (pinfunction "GND_GND") (pintype "bidirectional"))
      (node (ref "JP8") (pin "1") (pinfunction "1_1") (pintype "passive"))
      (node (ref "JP9") (pin "1") (pinfunction "1_1") (pintype "passive"))
      (node (ref "POWER") (pin "C") (pinfunction "C_C") (pintype "passive"))
      (node (ref "Q1") (pin "2") (pinfunction "2_2") (pintype "passive"))
      (node (ref "Q2") (pin "3") (pinfunction "S_3") (pintype "passive"))
      (node (ref "R1") (pin "1") (pinfunction "1_1") (pintype "passive"))
      (node (ref "R10") (pin "1") (pinfunction "1_1") (pintype "passive"))
      (node (ref "R11") (pin "1") (pinfunction "1_1") (pintype "passive"))
      (node (ref "R12") (pin "1") (pinfunction "1_1") (pintype "passive"))
      (node (ref "R13") (pin "1") (pinfunction "1_1") (pintype "passive"))
      (node (ref "R15") (pin "1") (pinfunction "1_1") (pintype "passive"))
      (node (ref "R17") (pin "1") (pinfunction "1_1") (pintype "passive"))
      (node (ref "R19") (pin "1") (pinfunction "1_1") (pintype "passive"))
      (node (ref "R2") (pin "1") (pinfunction "1_1") (pintype "passive"))
      (node (ref "R20") (pin "1") (pinfunction "1_1") (pintype "passive"))
      (node (ref "R21") (pin "1") (pinfunction "1_1") (pintype "passive"))
      (node (ref "R22") (pin "1") (pinfunction "1_1") (pintype "passive"))
      (node (ref "R24") (pin "1") (pinfunction "1_1") (pintype "passive"))
      (node (ref "R26") (pin "1") (pinfunction "1_1") (pintype "passive"))
      (node (ref "R3") (pin "1") (pinfunction "1_1") (pintype "passive"))
      (node (ref "R4") (pin "1") (pinfunction "1_1") (pintype "passive"))
      (node (ref "R5") (pin "1") (pinfunction "1_1") (pintype "passive"))
      (node (ref "R52") (pin "2") (pinfunction "2_2") (pintype "passive"))
      (node (ref "R8") (pin "1") (pinfunction "1_1") (pintype "passive"))
      (node (ref "S4") (pin "1") (pinfunction "1_1") (pintype "passive"))
      (node (ref "S5") (pin "3") (pinfunction "3_3") (pintype "bidirectional"))
      (node (ref "S5") (pin "4") (pinfunction "4_4") (pintype "bidirectional"))
      (node (ref "U1") (pin "21") (pinfunction "AGND_21") (pintype "bidirectional"))
      (node (ref "U1") (pin "3") (pinfunction "GND_3") (pintype "bidirectional"))
      (node (ref "U1") (pin "5") (pinfunction "GND_5") (pintype "bidirectional"))
      (node (ref "U10") (pin "3") (pinfunction "GND_3") (pintype "input"))
      (node (ref "U2") (pin "18") (pinfunction "GND18_18") (pintype "power_in"))
      (node (ref "U2") (pin "21") (pinfunction "GND21_21") (pintype "power_in"))
      (node (ref "U2") (pin "25") (pinfunction "AGND_25") (pintype "power_in"))
      (node (ref "U2") (pin "26") (pinfunction "TEST_26") (pintype "input"))
      (node (ref "U2") (pin "7") (pinfunction "GND7_7") (pintype "power_in"))
      (node (ref "U3") (pin "3") (pinfunction "GND_3") (pintype "bidirectional"))
      (node (ref "U4") (pin "5") (pinfunction "SGND_5") (pintype "bidirectional"))
      (node (ref "U4") (pin "PAD") (pinfunction "PAD_GND_PAD") (pintype "bidirectional"))
      (node (ref "U5") (pin "16") (pinfunction "SRN_16") (pintype "bidirectional"))
      (node (ref "U5") (pin "21") (pinfunction "GND_21") (pintype "bidirectional"))
      (node (ref "U5") (pin "7") (pinfunction "GND_7") (pintype "bidirectional"))
      (node (ref "U5") (pin "GND@10") (pinfunction "PAD_GND@10") (pintype "bidirectional"))
      (node (ref "U5") (pin "GND@11") (pinfunction "PAD_GND@11") (pintype "bidirectional"))
      (node (ref "U5") (pin "GND@12") (pinfunction "PAD_GND@12") (pintype "bidirectional"))
      (node (ref "U5") (pin "GND@13") (pinfunction "PAD_GND@13") (pintype "bidirectional"))
      (node (ref "U5") (pin "GND@14") (pinfunction "PAD_GND@14") (pintype "bidirectional"))
      (node (ref "U5") (pin "GND@15") (pinfunction "PAD_GND@15") (pintype "bidirectional"))
      (node (ref "U5") (pin "GND@16") (pinfunction "PAD_GND@16") (pintype "bidirectional"))
      (node (ref "U5") (pin "GND@17") (pinfunction "PAD_GND@17") (pintype "bidirectional"))
      (node (ref "U5") (pin "GND@18") (pinfunction "PAD_GND@18") (pintype "bidirectional"))
      (node (ref "U5") (pin "GND@19") (pinfunction "PAD_GND@19") (pintype "bidirectional"))
      (node (ref "U5") (pin "GND@20") (pinfunction "PAD_GND@20") (pintype "bidirectional"))
      (node (ref "U5") (pin "GND@21") (pinfunction "PAD_GND@21") (pintype "bidirectional"))
      (node (ref "U5") (pin "GND@22") (pinfunction "PAD_GND@22") (pintype "bidirectional"))
      (node (ref "U5") (pin "GND@23") (pinfunction "PAD_GND@23") (pintype "bidirectional"))
      (node (ref "U5") (pin "GND@24") (pinfunction "PAD_GND@24") (pintype "bidirectional"))
      (node (ref "U5") (pin "GND@25") (pinfunction "PAD_GND@25") (pintype "bidirectional"))
      (node (ref "U5") (pin "GND@26") (pinfunction "PAD_GND@26") (pintype "bidirectional"))
      (node (ref "U5") (pin "GND@27") (pinfunction "PAD_GND@27") (pintype "bidirectional"))
      (node (ref "U5") (pin "GND@28") (pinfunction "PAD_GND@28") (pintype "bidirectional"))
      (node (ref "U5") (pin "GND@29") (pinfunction "PAD_GND@29") (pintype "bidirectional"))
      (node (ref "U5") (pin "GND@30") (pinfunction "PAD_GND@30") (pintype "bidirectional"))
      (node (ref "U5") (pin "GND@PAD") (pinfunction "PAD_GND@PAD") (pintype "bidirectional"))
      (node (ref "U6") (pin "7") (pinfunction "GND_7") (pintype "power_in"))
      (node (ref "U7") (pin "3") (pinfunction "GND_3") (pintype "bidirectional"))
      (node (ref "U8") (pin "16") (pinfunction "SRN_16") (pintype "bidirectional"))
      (node (ref "U8") (pin "21") (pinfunction "GND_21") (pintype "bidirectional"))
      (node (ref "U8") (pin "7") (pinfunction "GND_7") (pintype "bidirectional"))
      (node (ref "U8") (pin "GND@10") (pinfunction "PAD_GND@10") (pintype "bidirectional"))
      (node (ref "U8") (pin "GND@11") (pinfunction "PAD_GND@11") (pintype "bidirectional"))
      (node (ref "U8") (pin "GND@12") (pinfunction "PAD_GND@12") (pintype "bidirectional"))
      (node (ref "U8") (pin "GND@13") (pinfunction "PAD_GND@13") (pintype "bidirectional"))
      (node (ref "U8") (pin "GND@14") (pinfunction "PAD_GND@14") (pintype "bidirectional"))
      (node (ref "U8") (pin "GND@15") (pinfunction "PAD_GND@15") (pintype "bidirectional"))
      (node (ref "U8") (pin "GND@16") (pinfunction "PAD_GND@16") (pintype "bidirectional"))
      (node (ref "U8") (pin "GND@17") (pinfunction "PAD_GND@17") (pintype "bidirectional"))
      (node (ref "U8") (pin "GND@18") (pinfunction "PAD_GND@18") (pintype "bidirectional"))
      (node (ref "U8") (pin "GND@19") (pinfunction "PAD_GND@19") (pintype "bidirectional"))
      (node (ref "U8") (pin "GND@20") (pinfunction "PAD_GND@20") (pintype "bidirectional"))
      (node (ref "U8") (pin "GND@21") (pinfunction "PAD_GND@21") (pintype "bidirectional"))
      (node (ref "U8") (pin "GND@22") (pinfunction "PAD_GND@22") (pintype "bidirectional"))
      (node (ref "U8") (pin "GND@23") (pinfunction "PAD_GND@23") (pintype "bidirectional"))
      (node (ref "U8") (pin "GND@24") (pinfunction "PAD_GND@24") (pintype "bidirectional"))
      (node (ref "U8") (pin "GND@25") (pinfunction "PAD_GND@25") (pintype "bidirectional"))
      (node (ref "U8") (pin "GND@26") (pinfunction "PAD_GND@26") (pintype "bidirectional"))
      (node (ref "U8") (pin "GND@27") (pinfunction "PAD_GND@27") (pintype "bidirectional"))
      (node (ref "U8") (pin "GND@28") (pinfunction "PAD_GND@28") (pintype "bidirectional"))
      (node (ref "U8") (pin "GND@29") (pinfunction "PAD_GND@29") (pintype "bidirectional"))
      (node (ref "U8") (pin "GND@30") (pinfunction "PAD_GND@30") (pintype "bidirectional"))
      (node (ref "U8") (pin "GND@PAD") (pinfunction "PAD_GND@PAD") (pintype "bidirectional"))
      (node (ref "U9") (pin "16") (pinfunction "SRN_16") (pintype "bidirectional"))
      (node (ref "U9") (pin "21") (pinfunction "GND_21") (pintype "bidirectional"))
      (node (ref "U9") (pin "7") (pinfunction "GND_7") (pintype "bidirectional"))
      (node (ref "U9") (pin "GND@10") (pinfunction "PAD_GND@10") (pintype "bidirectional"))
      (node (ref "U9") (pin "GND@11") (pinfunction "PAD_GND@11") (pintype "bidirectional"))
      (node (ref "U9") (pin "GND@12") (pinfunction "PAD_GND@12") (pintype "bidirectional"))
      (node (ref "U9") (pin "GND@13") (pinfunction "PAD_GND@13") (pintype "bidirectional"))
      (node (ref "U9") (pin "GND@14") (pinfunction "PAD_GND@14") (pintype "bidirectional"))
      (node (ref "U9") (pin "GND@15") (pinfunction "PAD_GND@15") (pintype "bidirectional"))
      (node (ref "U9") (pin "GND@16") (pinfunction "PAD_GND@16") (pintype "bidirectional"))
      (node (ref "U9") (pin "GND@17") (pinfunction "PAD_GND@17") (pintype "bidirectional"))
      (node (ref "U9") (pin "GND@18") (pinfunction "PAD_GND@18") (pintype "bidirectional"))
      (node (ref "U9") (pin "GND@19") (pinfunction "PAD_GND@19") (pintype "bidirectional"))
      (node (ref "U9") (pin "GND@20") (pinfunction "PAD_GND@20") (pintype "bidirectional"))
      (node (ref "U9") (pin "GND@21") (pinfunction "PAD_GND@21") (pintype "bidirectional"))
      (node (ref "U9") (pin "GND@22") (pinfunction "PAD_GND@22") (pintype "bidirectional"))
      (node (ref "U9") (pin "GND@23") (pinfunction "PAD_GND@23") (pintype "bidirectional"))
      (node (ref "U9") (pin "GND@24") (pinfunction "PAD_GND@24") (pintype "bidirectional"))
      (node (ref "U9") (pin "GND@25") (pinfunction "PAD_GND@25") (pintype "bidirectional"))
      (node (ref "U9") (pin "GND@26") (pinfunction "PAD_GND@26") (pintype "bidirectional"))
      (node (ref "U9") (pin "GND@27") (pinfunction "PAD_GND@27") (pintype "bidirectional"))
      (node (ref "U9") (pin "GND@28") (pinfunction "PAD_GND@28") (pintype "bidirectional"))
      (node (ref "U9") (pin "GND@29") (pinfunction "PAD_GND@29") (pintype "bidirectional"))
      (node (ref "U9") (pin "GND@30") (pinfunction "PAD_GND@30") (pintype "bidirectional"))
      (node (ref "U9") (pin "GND@PAD") (pinfunction "PAD_GND@PAD") (pintype "bidirectional"))
    )
    (net (code "23") (name "MISO-D12-LIMIT-Z") (class "Default")
      (node (ref "J1") (pin "1") (pinfunction "1_1") (pintype "passive"))
      (node (ref "U1") (pin "16") (pinfunction "PB4(MISO)_16") (pintype "bidirectional"))
      (node (ref "U6") (pin "6") (pinfunction "3Y_6") (pintype "output"))
    )
    (net (code "24") (name "MOSI-D11-SPINDLE_PWM") (class "Default")
      (node (ref "J1") (pin "4") (pinfunction "4_4") (pintype "passive"))
      (node (ref "U1") (pin "15") (pinfunction "PB3(MOSI/OC2)_15") (pintype "bidirectional"))
    )
    (net (code "25") (name "Net-(D1-PadA)") (class "Default")
      (node (ref "D1") (pin "A") (pinfunction "A_A") (pintype "passive"))
      (node (ref "R18") (pin "1") (pinfunction "1_1") (pintype "passive"))
    )
    (net (code "26") (name "Net-(D2-PadA)") (class "Default")
      (node (ref "D2") (pin "A") (pinfunction "A_A") (pintype "passive"))
      (node (ref "R9") (pin "1") (pinfunction "1_1") (pintype "passive"))
    )
    (net (code "27") (name "Net-(D4-PadA)") (class "Default")
      (node (ref "D4") (pin "A") (pinfunction "A_A") (pintype "passive"))
      (node (ref "R39") (pin "1") (pinfunction "1_1") (pintype "passive"))
    )
    (net (code "28") (name "Net-(D5-PadA)") (class "Default")
      (node (ref "D5") (pin "A") (pinfunction "A_A") (pintype "passive"))
      (node (ref "R32") (pin "1") (pinfunction "1_1") (pintype "passive"))
    )
    (net (code "29") (name "Net-(D6-PadA)") (class "Default")
      (node (ref "D6") (pin "A") (pinfunction "A_A") (pintype "passive"))
      (node (ref "R31") (pin "1") (pinfunction "1_1") (pintype "passive"))
    )
    (net (code "30") (name "Net-(D7-PadA)") (class "Default")
      (node (ref "D7") (pin "A") (pinfunction "A_A") (pintype "passive"))
      (node (ref "R40") (pin "1") (pinfunction "1_1") (pintype "passive"))
    )
    (net (code "31") (name "Net-(D8-PadA)") (class "Default")
      (node (ref "D8") (pin "A") (pinfunction "A_A") (pintype "passive"))
      (node (ref "R43") (pin "1") (pinfunction "1_1") (pintype "passive"))
    )
    (net (code "32") (name "Net-(D9-PadA)") (class "Default")
      (node (ref "D9") (pin "A") (pinfunction "A_A") (pintype "passive"))
      (node (ref "R42") (pin "1") (pinfunction "1_1") (pintype "passive"))
    )
    (net (code "33") (name "Net-(D10-PadA)") (class "Default")
      (node (ref "D10") (pin "A") (pinfunction "A_A") (pintype "passive"))
      (node (ref "R41") (pin "1") (pinfunction "1_1") (pintype "passive"))
    )
    (net (code "34") (name "Net-(D11-PadA)") (class "Default")
      (node (ref "D11") (pin "A") (pinfunction "A_A") (pintype "passive"))
      (node (ref "R44") (pin "1") (pinfunction "1_1") (pintype "passive"))
    )
    (net (code "35") (name "Net-(D12-PadA)") (class "Default")
      (node (ref "D12") (pin "A") (pinfunction "A_A") (pintype "passive"))
      (node (ref "R47") (pin "1") (pinfunction "1_1") (pintype "passive"))
    )
    (net (code "36") (name "Net-(D13-PadA)") (class "Default")
      (node (ref "D13") (pin "A") (pinfunction "A_A") (pintype "passive"))
      (node (ref "R46") (pin "1") (pinfunction "1_1") (pintype "passive"))
    )
    (net (code "37") (name "Net-(D14-PadA)") (class "Default")
      (node (ref "D14") (pin "A") (pinfunction "A_A") (pintype "passive"))
      (node (ref "R45") (pin "1") (pinfunction "1_1") (pintype "passive"))
    )
    (net (code "38") (name "Net-(D15-PadA)") (class "Default")
      (node (ref "D15") (pin "A") (pinfunction "A_A") (pintype "passive"))
      (node (ref "R49") (pin "1") (pinfunction "1_1") (pintype "passive"))
    )
    (net (code "39") (name "Net-(D16-PadA)") (class "Default")
      (node (ref "D16") (pin "A") (pinfunction "A_A") (pintype "passive"))
      (node (ref "F1") (pin "2") (pinfunction "2_2") (pintype "bidirectional"))
    )
    (net (code "40") (name "Net-(JP1-Pad1)") (class "Default")
      (node (ref "JP1") (pin "1") (pinfunction "1_1") (pintype "passive"))
      (node (ref "JP3") (pin "1") (pinfunction "1_1") (pintype "passive"))
      (node (ref "JP4") (pin "1") (pinfunction "1_1") (pintype "passive"))
      (node (ref "S5") (pin "5") (pinfunction "5_5") (pintype "bidirectional"))
    )
    (net (code "41") (name "Net-(JP1-Pad2)") (class "Default")
      (node (ref "JP1") (pin "2") (pinfunction "2_2") (pintype "passive"))
      (node (ref "R30") (pin "1") (pinfunction "1_1") (pintype "passive"))
      (node (ref "R38") (pin "2") (pinfunction "2_2") (pintype "passive"))
    )
    (net (code "42") (name "Net-(JP3-Pad2)") (class "Default")
      (node (ref "JP3") (pin "2") (pinfunction "2_2") (pintype "passive"))
      (node (ref "R27") (pin "2") (pinfunction "2_2") (pintype "passive"))
      (node (ref "R33") (pin "1") (pinfunction "1_1") (pintype "passive"))
    )
    (net (code "43") (name "Net-(JP4-Pad2)") (class "Default")
      (node (ref "JP4") (pin "2") (pinfunction "2_2") (pintype "passive"))
      (node (ref "R28") (pin "2") (pinfunction "2_2") (pintype "passive"))
      (node (ref "R34") (pin "1") (pinfunction "1_1") (pintype "passive"))
    )
    (net (code "44") (name "Net-(JP8-Pad2)") (class "Default")
      (node (ref "JP8") (pin "2") (pinfunction "2_2") (pintype "passive"))
      (node (ref "R29") (pin "2") (pinfunction "2_2") (pintype "passive"))
      (node (ref "R36") (pin "1") (pinfunction "1_1") (pintype "passive"))
    )
    (net (code "45") (name "Net-(JP9-Pad2)") (class "Default")
      (node (ref "JP9") (pin "2") (pinfunction "2_2") (pintype "passive"))
      (node (ref "R35") (pin "2") (pinfunction "2_2") (pintype "passive"))
      (node (ref "R48") (pin "1") (pinfunction "1_1") (pintype "passive"))
    )
    (net (code "46") (name "Net-(L1-1)") (class "Default")
      (node (ref "C7") (pin "2") (pinfunction "2_2") (pintype "passive"))
      (node (ref "D17") (pin "C") (pinfunction "C_C") (pintype "passive"))
      (node (ref "L1") (pin "P$1") (pinfunction "1_P$1") (pintype "passive"))
      (node (ref "U4") (pin "9") (pinfunction "SW_9") (pintype "bidirectional"))
    )
    (net (code "47") (name "Net-(POT1-A)") (class "Default")
      (node (ref "POT1") (pin "1") (pinfunction "A_1") (pintype "passive"))
      (node (ref "R1") (pin "2") (pinfunction "2_2") (pintype "passive"))
    )
    (net (code "48") (name "Net-(POT1-E)") (class "Default")
      (node (ref "POT1") (pin "3") (pinfunction "E_3") (pintype "passive"))
      (node (ref "R37") (pin "1") (pinfunction "1_1") (pintype "passive"))
    )
    (net (code "49") (name "Net-(POT1-S)") (class "Default")
      (node (ref "POT1") (pin "2") (pinfunction "S_2") (pintype "passive"))
      (node (ref "U5") (pin "8") (pinfunction "VREF_8") (pintype "bidirectional"))
    )
    (net (code "50") (name "Net-(POT2-A)") (class "Default")
      (node (ref "POT2") (pin "1") (pinfunction "A_1") (pintype "passive"))
      (node (ref "R17") (pin "2") (pinfunction "2_2") (pintype "passive"))
    )
    (net (code "51") (name "Net-(POT2-E)") (class "Default")
      (node (ref "POT2") (pin "3") (pinfunction "E_3") (pintype "passive"))
      (node (ref "R16") (pin "1") (pinfunction "1_1") (pintype "passive"))
    )
    (net (code "52") (name "Net-(POT2-S)") (class "Default")
      (node (ref "POT2") (pin "2") (pinfunction "S_2") (pintype "passive"))
      (node (ref "U8") (pin "8") (pinfunction "VREF_8") (pintype "bidirectional"))
    )
    (net (code "53") (name "Net-(POT3-A)") (class "Default")
      (node (ref "POT3") (pin "1") (pinfunction "A_1") (pintype "passive"))
      (node (ref "R26") (pin "2") (pinfunction "2_2") (pintype "passive"))
    )
    (net (code "54") (name "Net-(POT3-E)") (class "Default")
      (node (ref "POT3") (pin "3") (pinfunction "E_3") (pintype "passive"))
      (node (ref "R25") (pin "1") (pinfunction "1_1") (pintype "passive"))
    )
    (net (code "55") (name "Net-(POT3-S)") (class "Default")
      (node (ref "POT3") (pin "2") (pinfunction "S_2") (pintype "passive"))
      (node (ref "U9") (pin "8") (pinfunction "VREF_8") (pintype "bidirectional"))
    )
    (net (code "56") (name "Net-(POWER-PadA)") (class "Default")
      (node (ref "POWER") (pin "A") (pinfunction "A_A") (pintype "passive"))
      (node (ref "R56") (pin "2") (pinfunction "2_2") (pintype "passive"))
    )
    (net (code "57") (name "Net-(PROTECT-PadC)") (class "Default")
      (node (ref "PROTECT") (pin "C") (pinfunction "C_C") (pintype "passive"))
      (node (ref "R51") (pin "2") (pinfunction "2_2") (pintype "passive"))
    )
    (net (code "58") (name "Net-(Q2-D)") (class "Default")
      (node (ref "C2") (pin "1") (pinfunction "1_1") (pintype "passive"))
      (node (ref "JP6") (pin "GND") (pinfunction "GND_GND") (pintype "bidirectional"))
      (node (ref "PROTECT") (pin "A") (pinfunction "A_A") (pintype "passive"))
      (node (ref "Q2") (pin "2") (pinfunction "D_2") (pintype "passive"))
      (node (ref "VIN") (pin "1") (pinfunction "1_1") (pintype "passive"))
    )
    (net (code "59") (name "Net-(Q2-G)") (class "Default")
      (node (ref "Q2") (pin "1") (pinfunction "G_1") (pintype "passive"))
      (node (ref "R50") (pin "2") (pinfunction "2_2") (pintype "passive"))
    )
    (net (code "60") (name "Net-(R27-Pad1)") (class "Default")
      (node (ref "R27") (pin "1") (pinfunction "1_1") (pintype "passive"))
      (node (ref "R28") (pin "1") (pinfunction "1_1") (pintype "passive"))
      (node (ref "R38") (pin "1") (pinfunction "1_1") (pintype "passive"))
      (node (ref "S5") (pin "2") (pinfunction "2_2") (pintype "bidirectional"))
    )
    (net (code "61") (name "Net-(S1-P$1)") (class "Default")
      (node (ref "S1") (pin "1") (pinfunction "P$1_1") (pintype "bidirectional"))
      (node (ref "U5") (pin "12") (pinfunction "USM1_12") (pintype "bidirectional"))
    )
    (net (code "62") (name "Net-(S1-P$2)") (class "Default")
      (node (ref "S1") (pin "2") (pinfunction "P$2_2") (pintype "bidirectional"))
      (node (ref "U5") (pin "13") (pinfunction "USM0_13") (pintype "bidirectional"))
    )
    (net (code "63") (name "Net-(S2-P$1)") (class "Default")
      (node (ref "S2") (pin "1") (pinfunction "P$1_1") (pintype "bidirectional"))
      (node (ref "U8") (pin "12") (pinfunction "USM1_12") (pintype "bidirectional"))
    )
    (net (code "64") (name "Net-(S2-P$2)") (class "Default")
      (node (ref "S2") (pin "2") (pinfunction "P$2_2") (pintype "bidirectional"))
      (node (ref "U8") (pin "13") (pinfunction "USM0_13") (pintype "bidirectional"))
    )
    (net (code "65") (name "Net-(S3-P$1)") (class "Default")
      (node (ref "S3") (pin "1") (pinfunction "P$1_1") (pintype "bidirectional"))
      (node (ref "U9") (pin "12") (pinfunction "USM1_12") (pintype "bidirectional"))
    )
    (net (code "66") (name "Net-(S3-P$2)") (class "Default")
      (node (ref "S3") (pin "2") (pinfunction "P$2_2") (pintype "bidirectional"))
      (node (ref "U9") (pin "13") (pinfunction "USM0_13") (pintype "bidirectional"))
    )
    (net (code "67") (name "Net-(U1-PB6(XTAL1{slash}TOSC1))") (class "Default")
      (node (ref "Q1") (pin "1") (pinfunction "1_1") (pintype "passive"))
      (node (ref "U1") (pin "7") (pinfunction "PB6(XTAL1/TOSC1)_7") (pintype "bidirectional"))
    )
    (net (code "68") (name "Net-(U1-PB7(XTAL2{slash}TOSC2))") (class "Default")
      (node (ref "Q1") (pin "3") (pinfunction "3_3") (pintype "passive"))
      (node (ref "U1") (pin "8") (pinfunction "PB7(XTAL2/TOSC2)_8") (pintype "bidirectional"))
    )
    (net (code "69") (name "Net-(U2-RXLED)") (class "Default")
      (node (ref "D2") (pin "C") (pinfunction "C_C") (pintype "passive"))
      (node (ref "U2") (pin "22") (pinfunction "RXLED_22") (pintype "input"))
    )
    (net (code "70") (name "Net-(U2-TXLED)") (class "Default")
      (node (ref "D1") (pin "C") (pinfunction "C_C") (pintype "passive"))
      (node (ref "U2") (pin "23") (pinfunction "TXLED_23") (pintype "input"))
    )
    (net (code "71") (name "Net-(U2-USBDM)") (class "Default")
      (node (ref "JP5") (pin "D-") (pinfunction "D-_D-") (pintype "bidirectional"))
      (node (ref "U2") (pin "16") (pinfunction "USBDM_16") (pintype "bidirectional"))
    )
    (net (code "72") (name "Net-(U2-USBDP)") (class "Default")
      (node (ref "JP5") (pin "D+") (pinfunction "D+_D+") (pintype "bidirectional"))
      (node (ref "U2") (pin "15") (pinfunction "USBDP_15") (pintype "bidirectional"))
    )
    (net (code "73") (name "Net-(U3-A)") (class "Default")
      (node (ref "U3") (pin "2") (pinfunction "A_2") (pintype "bidirectional"))
      (node (ref "U6") (pin "10") (pinfunction "5Y_10") (pintype "output"))
    )
    (net (code "74") (name "Net-(U3-Y)") (class "Default")
      (node (ref "U3") (pin "4") (pinfunction "Y_4") (pintype "bidirectional"))
      (node (ref "U7") (pin "2") (pinfunction "B_2") (pintype "bidirectional"))
    )
    (net (code "75") (name "Net-(U4-BST)") (class "Default")
      (node (ref "C7") (pin "1") (pinfunction "1_1") (pintype "passive"))
      (node (ref "U4") (pin "10") (pinfunction "BST_10") (pintype "bidirectional"))
    )
    (net (code "76") (name "Net-(U4-CS)") (class "Default")
      (node (ref "D17") (pin "A") (pinfunction "A_A") (pintype "passive"))
      (node (ref "R54") (pin "2") (pinfunction "2_2") (pintype "passive"))
      (node (ref "U4") (pin "8") (pinfunction "CS_8") (pintype "bidirectional"))
    )
    (net (code "77") (name "Net-(U4-CSG)") (class "Default")
      (node (ref "R54") (pin "1") (pinfunction "1_1") (pintype "passive"))
      (node (ref "U4") (pin "7") (pinfunction "CSG_7") (pintype "bidirectional"))
    )
    (net (code "78") (name "Net-(U4-FB)") (class "Default")
      (node (ref "R52") (pin "1") (pinfunction "1_1") (pintype "passive"))
      (node (ref "R53") (pin "1") (pinfunction "1_1") (pintype "passive"))
      (node (ref "U4") (pin "6") (pinfunction "FB_6") (pintype "bidirectional"))
    )
    (net (code "79") (name "Net-(U4-RT)") (class "Default")
      (node (ref "R55") (pin "1") (pinfunction "1_1") (pintype "passive"))
      (node (ref "U4") (pin "2") (pinfunction "RT_2") (pintype "bidirectional"))
    )
    (net (code "80") (name "Net-(U4-SS)") (class "Default")
      (node (ref "C9") (pin "1") (pinfunction "1_1") (pintype "passive"))
      (node (ref "U4") (pin "4") (pinfunction "SS_4") (pintype "bidirectional"))
    )
    (net (code "81") (name "Net-(U5-AOUT1)") (class "Default")
      (node (ref "U5") (pin "4") (pinfunction "AOUT1_4") (pintype "bidirectional"))
      (node (ref "X-A") (pin "1") (pinfunction "1_1") (pintype "passive"))
    )
    (net (code "82") (name "Net-(U5-AOUT2)") (class "Default")
      (node (ref "U5") (pin "25") (pinfunction "AOUT2_25") (pintype "bidirectional"))
      (node (ref "X-A") (pin "2") (pinfunction "2_2") (pintype "passive"))
    )
    (net (code "83") (name "Net-(U5-BOUT1)") (class "Default")
      (node (ref "U5") (pin "11") (pinfunction "BOUT1_11") (pintype "bidirectional"))
      (node (ref "X-B") (pin "1") (pinfunction "1_1") (pintype "passive"))
    )
    (net (code "84") (name "Net-(U5-BOUT2)") (class "Default")
      (node (ref "U5") (pin "18") (pinfunction "BOUT2_18") (pintype "bidirectional"))
      (node (ref "X-B") (pin "2") (pinfunction "2_2") (pintype "passive"))
    )
    (net (code "85") (name "Net-(U5-CP1)") (class "Default")
      (node (ref "C16") (pin "2") (pinfunction "2_2") (pintype "passive"))
      (node (ref "U5") (pin "23") (pinfunction "CP1_23") (pintype "bidirectional"))
    )
    (net (code "86") (name "Net-(U5-CP2)") (class "Default")
      (node (ref "C16") (pin "1") (pinfunction "1_1") (pintype "passive"))
      (node (ref "U5") (pin "24") (pinfunction "CP2_24") (pintype "bidirectional"))
    )
    (net (code "87") (name "Net-(U5-DECAY)") (class "Default")
      (node (ref "C32") (pin "1") (pinfunction "1_1") (pintype "passive"))
      (node (ref "R14") (pin "1") (pinfunction "1_1") (pintype "passive"))
      (node (ref "R15") (pin "2") (pinfunction "2_2") (pintype "passive"))
      (node (ref "U5") (pin "5") (pinfunction "DECAY_5") (pintype "bidirectional"))
    )
    (net (code "88") (name "Net-(U5-ISENA)") (class "Default")
      (node (ref "C20") (pin "1") (pinfunction "1_1") (pintype "passive"))
      (node (ref "R10") (pin "2") (pinfunction "2_2") (pintype "passive"))
      (node (ref "U5") (pin "1") (pinfunction "ISENA_1") (pintype "bidirectional"))
    )
    (net (code "89") (name "Net-(U5-ISENB)") (class "Default")
      (node (ref "C19") (pin "1") (pinfunction "1_1") (pintype "passive"))
      (node (ref "R11") (pin "2") (pinfunction "2_2") (pintype "passive"))
      (node (ref "U5") (pin "14") (pinfunction "ISENB_14") (pintype "bidirectional"))
    )
    (net (code "90") (name "Net-(U5-RCA)") (class "Default")
      (node (ref "C21") (pin "1") (pinfunction "1_1") (pintype "passive"))
      (node (ref "R12") (pin "2") (pinfunction "2_2") (pintype "passive"))
      (node (ref "U5") (pin "6") (pinfunction "RCA_6") (pintype "bidirectional"))
    )
    (net (code "91") (name "Net-(U5-RCB)") (class "Default")
      (node (ref "C22") (pin "1") (pinfunction "1_1") (pintype "passive"))
      (node (ref "R13") (pin "2") (pinfunction "2_2") (pintype "passive"))
      (node (ref "U5") (pin "9") (pinfunction "RCB_9") (pintype "bidirectional"))
    )
    (net (code "92") (name "Net-(U5-VCP)") (class "Default")
      (node (ref "C17") (pin "2") (pinfunction "2_2") (pintype "passive"))
      (node (ref "U5") (pin "22") (pinfunction "VCP_22") (pintype "bidirectional"))
    )
    (net (code "93") (name "Net-(U5-VGD)") (class "Default")
      (node (ref "C18") (pin "2") (pinfunction "2_2") (pintype "passive"))
      (node (ref "U5") (pin "20") (pinfunction "VGD_20") (pintype "bidirectional"))
    )
    (net (code "94") (name "Net-(U8-AOUT1)") (class "Default")
      (node (ref "U8") (pin "4") (pinfunction "AOUT1_4") (pintype "bidirectional"))
      (node (ref "Y-A") (pin "1") (pinfunction "1_1") (pintype "passive"))
    )
    (net (code "95") (name "Net-(U8-AOUT2)") (class "Default")
      (node (ref "U8") (pin "25") (pinfunction "AOUT2_25") (pintype "bidirectional"))
      (node (ref "Y-A") (pin "2") (pinfunction "2_2") (pintype "passive"))
    )
    (net (code "96") (name "Net-(U8-BOUT1)") (class "Default")
      (node (ref "U8") (pin "11") (pinfunction "BOUT1_11") (pintype "bidirectional"))
      (node (ref "Y-B") (pin "1") (pinfunction "1_1") (pintype "passive"))
    )
    (net (code "97") (name "Net-(U8-BOUT2)") (class "Default")
      (node (ref "U8") (pin "18") (pinfunction "BOUT2_18") (pintype "bidirectional"))
      (node (ref "Y-B") (pin "2") (pinfunction "2_2") (pintype "passive"))
    )
    (net (code "98") (name "Net-(U8-CP1)") (class "Default")
      (node (ref "C1") (pin "2") (pinfunction "2_2") (pintype "passive"))
      (node (ref "U8") (pin "23") (pinfunction "CP1_23") (pintype "bidirectional"))
    )
    (net (code "99") (name "Net-(U8-CP2)") (class "Default")
      (node (ref "C1") (pin "1") (pinfunction "1_1") (pintype "passive"))
      (node (ref "U8") (pin "24") (pinfunction "CP2_24") (pintype "bidirectional"))
    )
    (net (code "100") (name "Net-(U8-DECAY)") (class "Default")
      (node (ref "C15") (pin "1") (pinfunction "1_1") (pintype "passive"))
      (node (ref "R7") (pin "1") (pinfunction "1_1") (pintype "passive"))
      (node (ref "R8") (pin "2") (pinfunction "2_2") (pintype "passive"))
      (node (ref "U8") (pin "5") (pinfunction "DECAY_5") (pintype "bidirectional"))
    )
    (net (code "101") (name "Net-(U8-ISENA)") (class "Default")
      (node (ref "C11") (pin "1") (pinfunction "1_1") (pintype "passive"))
      (node (ref "R2") (pin "2") (pinfunction "2_2") (pintype "passive"))
      (node (ref "U8") (pin "1") (pinfunction "ISENA_1") (pintype "bidirectional"))
    )
    (net (code "102") (name "Net-(U8-ISENB)") (class "Default")
      (node (ref "C10") (pin "1") (pinfunction "1_1") (pintype "passive"))
      (node (ref "R3") (pin "2") (pinfunction "2_2") (pintype "passive"))
      (node (ref "U8") (pin "14") (pinfunction "ISENB_14") (pintype "bidirectional"))
    )
    (net (code "103") (name "Net-(U8-RCA)") (class "Default")
      (node (ref "C12") (pin "1") (pinfunction "1_1") (pintype "passive"))
      (node (ref "R4") (pin "2") (pinfunction "2_2") (pintype "passive"))
      (node (ref "U8") (pin "6") (pinfunction "RCA_6") (pintype "bidirectional"))
    )
    (net (code "104") (name "Net-(U8-RCB)") (class "Default")
      (node (ref "C13") (pin "1") (pinfunction "1_1") (pintype "passive"))
      (node (ref "R5") (pin "2") (pinfunction "2_2") (pintype "passive"))
      (node (ref "U8") (pin "9") (pinfunction "RCB_9") (pintype "bidirectional"))
    )
    (net (code "105") (name "Net-(U8-VCP)") (class "Default")
      (node (ref "C6") (pin "2") (pinfunction "2_2") (pintype "passive"))
      (node (ref "U8") (pin "22") (pinfunction "VCP_22") (pintype "bidirectional"))
    )
    (net (code "106") (name "Net-(U8-VGD)") (class "Default")
      (node (ref "C8") (pin "2") (pinfunction "2_2") (pintype "passive"))
      (node (ref "U8") (pin "20") (pinfunction "VGD_20") (pintype "bidirectional"))
    )
    (net (code "107") (name "Net-(U9-AOUT1)") (class "Default")
      (node (ref "U9") (pin "4") (pinfunction "AOUT1_4") (pintype "bidirectional"))
      (node (ref "Z-A") (pin "1") (pinfunction "1_1") (pintype "passive"))
    )
    (net (code "108") (name "Net-(U9-AOUT2)") (class "Default")
      (node (ref "U9") (pin "25") (pinfunction "AOUT2_25") (pintype "bidirectional"))
      (node (ref "Z-A") (pin "2") (pinfunction "2_2") (pintype "passive"))
    )
    (net (code "109") (name "Net-(U9-BOUT1)") (class "Default")
      (node (ref "U9") (pin "11") (pinfunction "BOUT1_11") (pintype "bidirectional"))
      (node (ref "Z-B") (pin "1") (pinfunction "1_1") (pintype "passive"))
    )
    (net (code "110") (name "Net-(U9-BOUT2)") (class "Default")
      (node (ref "U9") (pin "18") (pinfunction "BOUT2_18") (pintype "bidirectional"))
      (node (ref "Z-B") (pin "2") (pinfunction "2_2") (pintype "passive"))
    )
    (net (code "111") (name "Net-(U9-CP1)") (class "Default")
      (node (ref "C27") (pin "2") (pinfunction "2_2") (pintype "passive"))
      (node (ref "U9") (pin "23") (pinfunction "CP1_23") (pintype "bidirectional"))
    )
    (net (code "112") (name "Net-(U9-CP2)") (class "Default")
      (node (ref "C27") (pin "1") (pinfunction "1_1") (pintype "passive"))
      (node (ref "U9") (pin "24") (pinfunction "CP2_24") (pintype "bidirectional"))
    )
    (net (code "113") (name "Net-(U9-DECAY)") (class "Default")
      (node (ref "C36") (pin "1") (pinfunction "1_1") (pintype "passive"))
      (node (ref "R23") (pin "1") (pinfunction "1_1") (pintype "passive"))
      (node (ref "R24") (pin "2") (pinfunction "2_2") (pintype "passive"))
      (node (ref "U9") (pin "5") (pinfunction "DECAY_5") (pintype "bidirectional"))
    )
    (net (code "114") (name "Net-(U9-ISENA)") (class "Default")
      (node (ref "C31") (pin "1") (pinfunction "1_1") (pintype "passive"))
      (node (ref "R19") (pin "2") (pinfunction "2_2") (pintype "passive"))
      (node (ref "U9") (pin "1") (pinfunction "ISENA_1") (pintype "bidirectional"))
    )
    (net (code "115") (name "Net-(U9-ISENB)") (class "Default")
      (node (ref "C30") (pin "1") (pinfunction "1_1") (pintype "passive"))
      (node (ref "R20") (pin "2") (pinfunction "2_2") (pintype "passive"))
      (node (ref "U9") (pin "14") (pinfunction "ISENB_14") (pintype "bidirectional"))
    )
    (net (code "116") (name "Net-(U9-RCA)") (class "Default")
      (node (ref "C33") (pin "1") (pinfunction "1_1") (pintype "passive"))
      (node (ref "R21") (pin "2") (pinfunction "2_2") (pintype "passive"))
      (node (ref "U9") (pin "6") (pinfunction "RCA_6") (pintype "bidirectional"))
    )
    (net (code "117") (name "Net-(U9-RCB)") (class "Default")
      (node (ref "C34") (pin "1") (pinfunction "1_1") (pintype "passive"))
      (node (ref "R22") (pin "2") (pinfunction "2_2") (pintype "passive"))
      (node (ref "U9") (pin "9") (pinfunction "RCB_9") (pintype "bidirectional"))
    )
    (net (code "118") (name "Net-(U9-VCP)") (class "Default")
      (node (ref "C28") (pin "2") (pinfunction "2_2") (pintype "passive"))
      (node (ref "U9") (pin "22") (pinfunction "VCP_22") (pintype "bidirectional"))
    )
    (net (code "119") (name "Net-(U9-VGD)") (class "Default")
      (node (ref "C29") (pin "2") (pinfunction "2_2") (pintype "passive"))
      (node (ref "U9") (pin "20") (pinfunction "VGD_20") (pintype "bidirectional"))
    )
    (net (code "120") (name "PROBE") (class "Default")
      (node (ref "C57") (pin "1") (pinfunction "1_1") (pintype "passive"))
      (node (ref "D11") (pin "C") (pinfunction "C_C") (pintype "passive"))
      (node (ref "R36") (pin "2") (pinfunction "2_2") (pintype "passive"))
      (node (ref "U6") (pin "9") (pinfunction "4A_9") (pintype "input"))
    )
    (net (code "121") (name "RESET") (class "Default")
      (node (ref "C52") (pin "1") (pinfunction "1_1") (pintype "passive"))
      (node (ref "J1") (pin "5") (pinfunction "5_5") (pintype "passive"))
      (node (ref "JP17") (pin "6") (pinfunction "6_6") (pintype "passive"))
      (node (ref "R6") (pin "1") (pinfunction "1_1") (pintype "passive"))
      (node (ref "S4") (pin "3") (pinfunction "2_3") (pintype "passive"))
      (node (ref "U1") (pin "29") (pinfunction "PC6(/RESET)_29") (pintype "bidirectional"))
    )
    (net (code "122") (name "RXI") (class "Default")
      (node (ref "JP17") (pin "9") (pinfunction "9_9") (pintype "passive"))
      (node (ref "U1") (pin "30") (pinfunction "PD0(RXD)_30") (pintype "bidirectional"))
      (node (ref "U2") (pin "1") (pinfunction "TXD_1") (pintype "output"))
    )
    (net (code "123") (name "SCK-D13-SPINDLE_DIR") (class "Default")
      (node (ref "J1") (pin "3") (pinfunction "3_3") (pintype "passive"))
      (node (ref "U1") (pin "17") (pinfunction "PB5(SCK)_17") (pintype "bidirectional"))
    )
    (net (code "124") (name "STEP_ENABLE") (class "Default")
      (node (ref "JP19") (pin "6") (pinfunction "6_6") (pintype "passive"))
      (node (ref "R49") (pin "2") (pinfunction "2_2") (pintype "passive"))
      (node (ref "U5") (pin "26") (pinfunction "ENABLEN_26") (pintype "bidirectional"))
      (node (ref "U7") (pin "4") (pinfunction "Y_4") (pintype "bidirectional"))
      (node (ref "U8") (pin "26") (pinfunction "ENABLEN_26") (pintype "bidirectional"))
      (node (ref "U9") (pin "26") (pinfunction "ENABLEN_26") (pintype "bidirectional"))
    )
    (net (code "125") (name "TXO") (class "Default")
      (node (ref "JP17") (pin "10") (pinfunction "10_10") (pintype "passive"))
      (node (ref "U1") (pin "31") (pinfunction "PD1(TXD)_31") (pintype "bidirectional"))
      (node (ref "U2") (pin "5") (pinfunction "RXD_5") (pintype "input"))
    )
    (net (code "126") (name "VCC") (class "Default")
      (node (ref "C42") (pin "1") (pinfunction "1_1") (pintype "passive"))
      (node (ref "JP15") (pin "2") (pinfunction "2_2") (pintype "passive"))
      (node (ref "JP16") (pin "5") (pinfunction "5_5") (pintype "passive"))
      (node (ref "JP16") (pin "7") (pinfunction "7_7") (pintype "passive"))
      (node (ref "U10") (pin "2") (pinfunction "OUT_2") (pintype "output"))
    )
    (net (code "127") (name "VCC_USB") (class "Default")
      (node (ref "C53") (pin "1") (pinfunction "1_1") (pintype "passive"))
      (node (ref "F1") (pin "1") (pinfunction "1_1") (pintype "bidirectional"))
      (node (ref "JP5") (pin "VBUS") (pinfunction "VBUS_VBUS") (pintype "bidirectional"))
      (node (ref "U2") (pin "20") (pinfunction "VCC_20") (pintype "power_in"))
      (node (ref "U2") (pin "4") (pinfunction "VCCIO_4") (pintype "power_in"))
    )
    (net (code "128") (name "VIN") (class "Default")
      (node (ref "C14") (pin "+") (pinfunction "+_+") (pintype "passive"))
      (node (ref "C17") (pin "1") (pinfunction "1_1") (pintype "passive"))
      (node (ref "C2") (pin "2") (pinfunction "2_2") (pintype "passive"))
      (node (ref "C23") (pin "+") (pinfunction "+_+") (pintype "passive"))
      (node (ref "C25") (pin "+") (pinfunction "+_+") (pintype "passive"))
      (node (ref "C26") (pin "+") (pinfunction "+_+") (pintype "passive"))
      (node (ref "C28") (pin "1") (pinfunction "1_1") (pintype "passive"))
      (node (ref "C35") (pin "+") (pinfunction "+_+") (pintype "passive"))
      (node (ref "C38") (pin "+") (pinfunction "+_+") (pintype "passive"))
      (node (ref "C4") (pin "1") (pinfunction "1_1") (pintype "passive"))
      (node (ref "C41") (pin "+") (pinfunction "+_+") (pintype "passive"))
      (node (ref "C43") (pin "1") (pinfunction "1_1") (pintype "passive"))
      (node (ref "C45") (pin "1") (pinfunction "1_1") (pintype "passive"))
      (node (ref "C46") (pin "1") (pinfunction "1_1") (pintype "passive"))
      (node (ref "C6") (pin "1") (pinfunction "1_1") (pintype "passive"))
      (node (ref "JP16") (pin "1") (pinfunction "1_1") (pintype "passive"))
      (node (ref "JP16") (pin "3") (pinfunction "3_3") (pintype "passive"))
      (node (ref "JP19") (pin "4") (pinfunction "4_4") (pintype "passive"))
      (node (ref "JP19") (pin "5") (pinfunction "5_5") (pintype "passive"))
      (node (ref "JP6") (pin "PWR") (pinfunction "PWR_PWR") (pintype "bidirectional"))
      (node (ref "R50") (pin "1") (pinfunction "1_1") (pintype "passive"))
      (node (ref "R51") (pin "1") (pinfunction "1_1") (pintype "passive"))
      (node (ref "R55") (pin "2") (pinfunction "2_2") (pintype "passive"))
      (node (ref "R56") (pin "1") (pinfunction "1_1") (pintype "passive"))
      (node (ref "U10") (pin "1") (pinfunction "IN_1") (pintype "input"))
      (node (ref "U4") (pin "1") (pinfunction "VIN_1") (pintype "bidirectional"))
      (node (ref "U5") (pin "15") (pinfunction "VMB_15") (pintype "bidirectional"))
      (node (ref "U5") (pin "28") (pinfunction "VMA_28") (pintype "bidirectional"))
      (node (ref "U8") (pin "15") (pinfunction "VMB_15") (pintype "bidirectional"))
      (node (ref "U8") (pin "28") (pinfunction "VMA_28") (pintype "bidirectional"))
      (node (ref "U9") (pin "15") (pinfunction "VMB_15") (pintype "bidirectional"))
      (node (ref "U9") (pin "28") (pinfunction "VMA_28") (pintype "bidirectional"))
      (node (ref "VIN") (pin "2") (pinfunction "2_2") (pintype "passive"))
    )
    (net (code "129") (name "X_LIM") (class "Default")
      (node (ref "C54") (pin "1") (pinfunction "1_1") (pintype "passive"))
      (node (ref "D6") (pin "C") (pinfunction "C_C") (pintype "passive"))
      (node (ref "R30") (pin "2") (pinfunction "2_2") (pintype "passive"))
      (node (ref "U6") (pin "1") (pinfunction "1A_1") (pintype "input"))
    )
    (net (code "130") (name "Y_LIM") (class "Default")
      (node (ref "C55") (pin "1") (pinfunction "1_1") (pintype "passive"))
      (node (ref "D10") (pin "C") (pinfunction "C_C") (pintype "passive"))
      (node (ref "R33") (pin "2") (pinfunction "2_2") (pintype "passive"))
      (node (ref "U6") (pin "3") (pinfunction "2A_3") (pintype "input"))
    )
    (net (code "131") (name "Z_LIM") (class "Default")
      (node (ref "C56") (pin "1") (pinfunction "1_1") (pintype "passive"))
      (node (ref "D14") (pin "C") (pinfunction "C_C") (pintype "passive"))
      (node (ref "R34") (pin "2") (pinfunction "2_2") (pintype "passive"))
      (node (ref "U6") (pin "5") (pinfunction "3A_5") (pintype "input"))
    )
    (net (code "132") (name "unconnected-(JP6-PadGNDBREAK)") (class "Default")
      (node (ref "JP6") (pin "GNDBREAK") (pinfunction "GNDBREAK_GNDBREAK") (pintype "bidirectional"))
    )
    (net (code "133") (name "unconnected-(U2-CTS-Pad11)") (class "Default")
      (node (ref "U2") (pin "11") (pinfunction "CTS_11") (pintype "input"))
    )
    (net (code "134") (name "unconnected-(U2-DCD-Pad10)") (class "Default")
      (node (ref "U2") (pin "10") (pinfunction "DCD_10") (pintype "input"))
    )
    (net (code "135") (name "unconnected-(U2-DSR-Pad9)") (class "Default")
      (node (ref "U2") (pin "9") (pinfunction "DSR_9") (pintype "input"))
    )
    (net (code "136") (name "unconnected-(U2-OSCI-Pad27)") (class "Default")
      (node (ref "U2") (pin "27") (pinfunction "OSCI_27") (pintype "input"))
    )
    (net (code "137") (name "unconnected-(U2-OSCO-Pad28)") (class "Default")
      (node (ref "U2") (pin "28") (pinfunction "OSCO_28") (pintype "output"))
    )
    (net (code "138") (name "unconnected-(U2-PWREN-Pad14)") (class "Default")
      (node (ref "U2") (pin "14") (pinfunction "PWREN_14") (pintype "input"))
    )
    (net (code "139") (name "unconnected-(U2-RESET-Pad19)") (class "Default")
      (node (ref "U2") (pin "19") (pinfunction "RESET_19") (pintype "input"))
    )
    (net (code "140") (name "unconnected-(U2-RI-Pad6)") (class "Default")
      (node (ref "U2") (pin "6") (pinfunction "RI_6") (pintype "input"))
    )
    (net (code "141") (name "unconnected-(U2-RTS-Pad3)") (class "Default")
      (node (ref "U2") (pin "3") (pinfunction "RTS_3") (pintype "output"))
    )
    (net (code "142") (name "unconnected-(U2-SLEEP-Pad12)") (class "Default")
      (node (ref "U2") (pin "12") (pinfunction "SLEEP_12") (pintype "input"))
    )
    (net (code "143") (name "unconnected-(U2-TXDEN-Pad13)") (class "Default")
      (node (ref "U2") (pin "13") (pinfunction "TXDEN_13") (pintype "input"))
    )
    (net (code "144") (name "unconnected-(U2-VCCD-Pad17)") (class "Default")
      (node (ref "U2") (pin "17") (pinfunction "VCCD_17") (pintype "output"))
    )
    (net (code "145") (name "unconnected-(U3-NC-Pad1)") (class "Default")
      (node (ref "U3") (pin "1") (pinfunction "NC_1") (pintype "bidirectional"))
    )
    (net (code "146") (name "unconnected-(U4-PGD-Pad3)") (class "Default")
      (node (ref "U4") (pin "3") (pinfunction "PGD_3") (pintype "bidirectional"))
    )
    (net (code "147") (name "unconnected-(U5-HOME-Pad2)") (class "Default")
      (node (ref "U5") (pin "2") (pinfunction "HOME_2") (pintype "bidirectional"))
    )
    (net (code "148") (name "unconnected-(U6-6A-Pad13)") (class "Default")
      (node (ref "U6") (pin "13") (pinfunction "6A_13") (pintype "input"))
    )
    (net (code "149") (name "unconnected-(U6-6Y-Pad12)") (class "Default")
      (node (ref "U6") (pin "12") (pinfunction "6Y_12") (pintype "output"))
    )
    (net (code "150") (name "unconnected-(U8-HOME-Pad2)") (class "Default")
      (node (ref "U8") (pin "2") (pinfunction "HOME_2") (pintype "bidirectional"))
    )
    (net (code "151") (name "unconnected-(U9-HOME-Pad2)") (class "Default")
      (node (ref "U9") (pin "2") (pinfunction "HOME_2") (pintype "bidirectional"))
    )
  )
)
